# altair.net
KiCad netlist of a schematic drawn in EAGLE
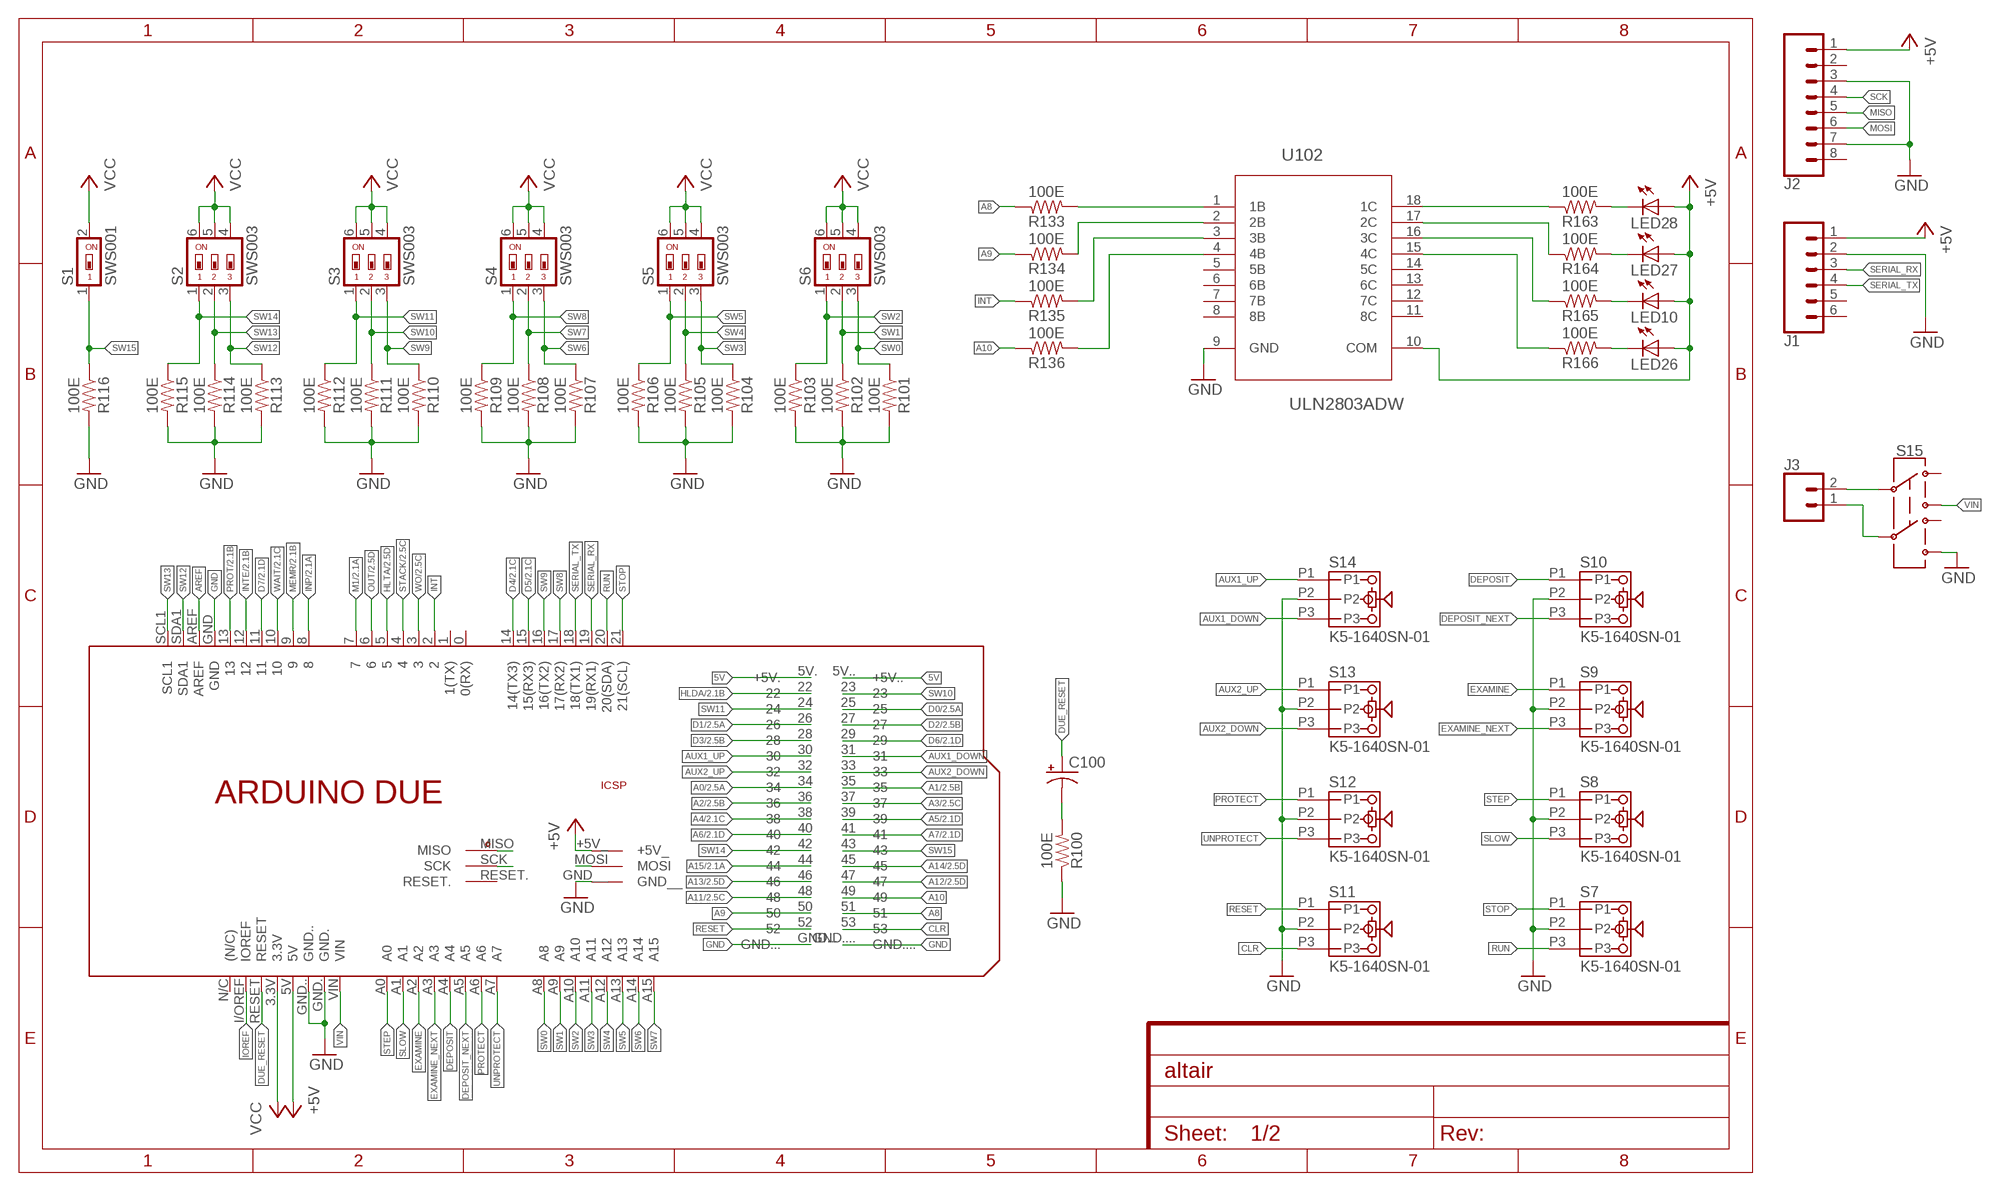
[diagram p0: schematic, sheet 1]
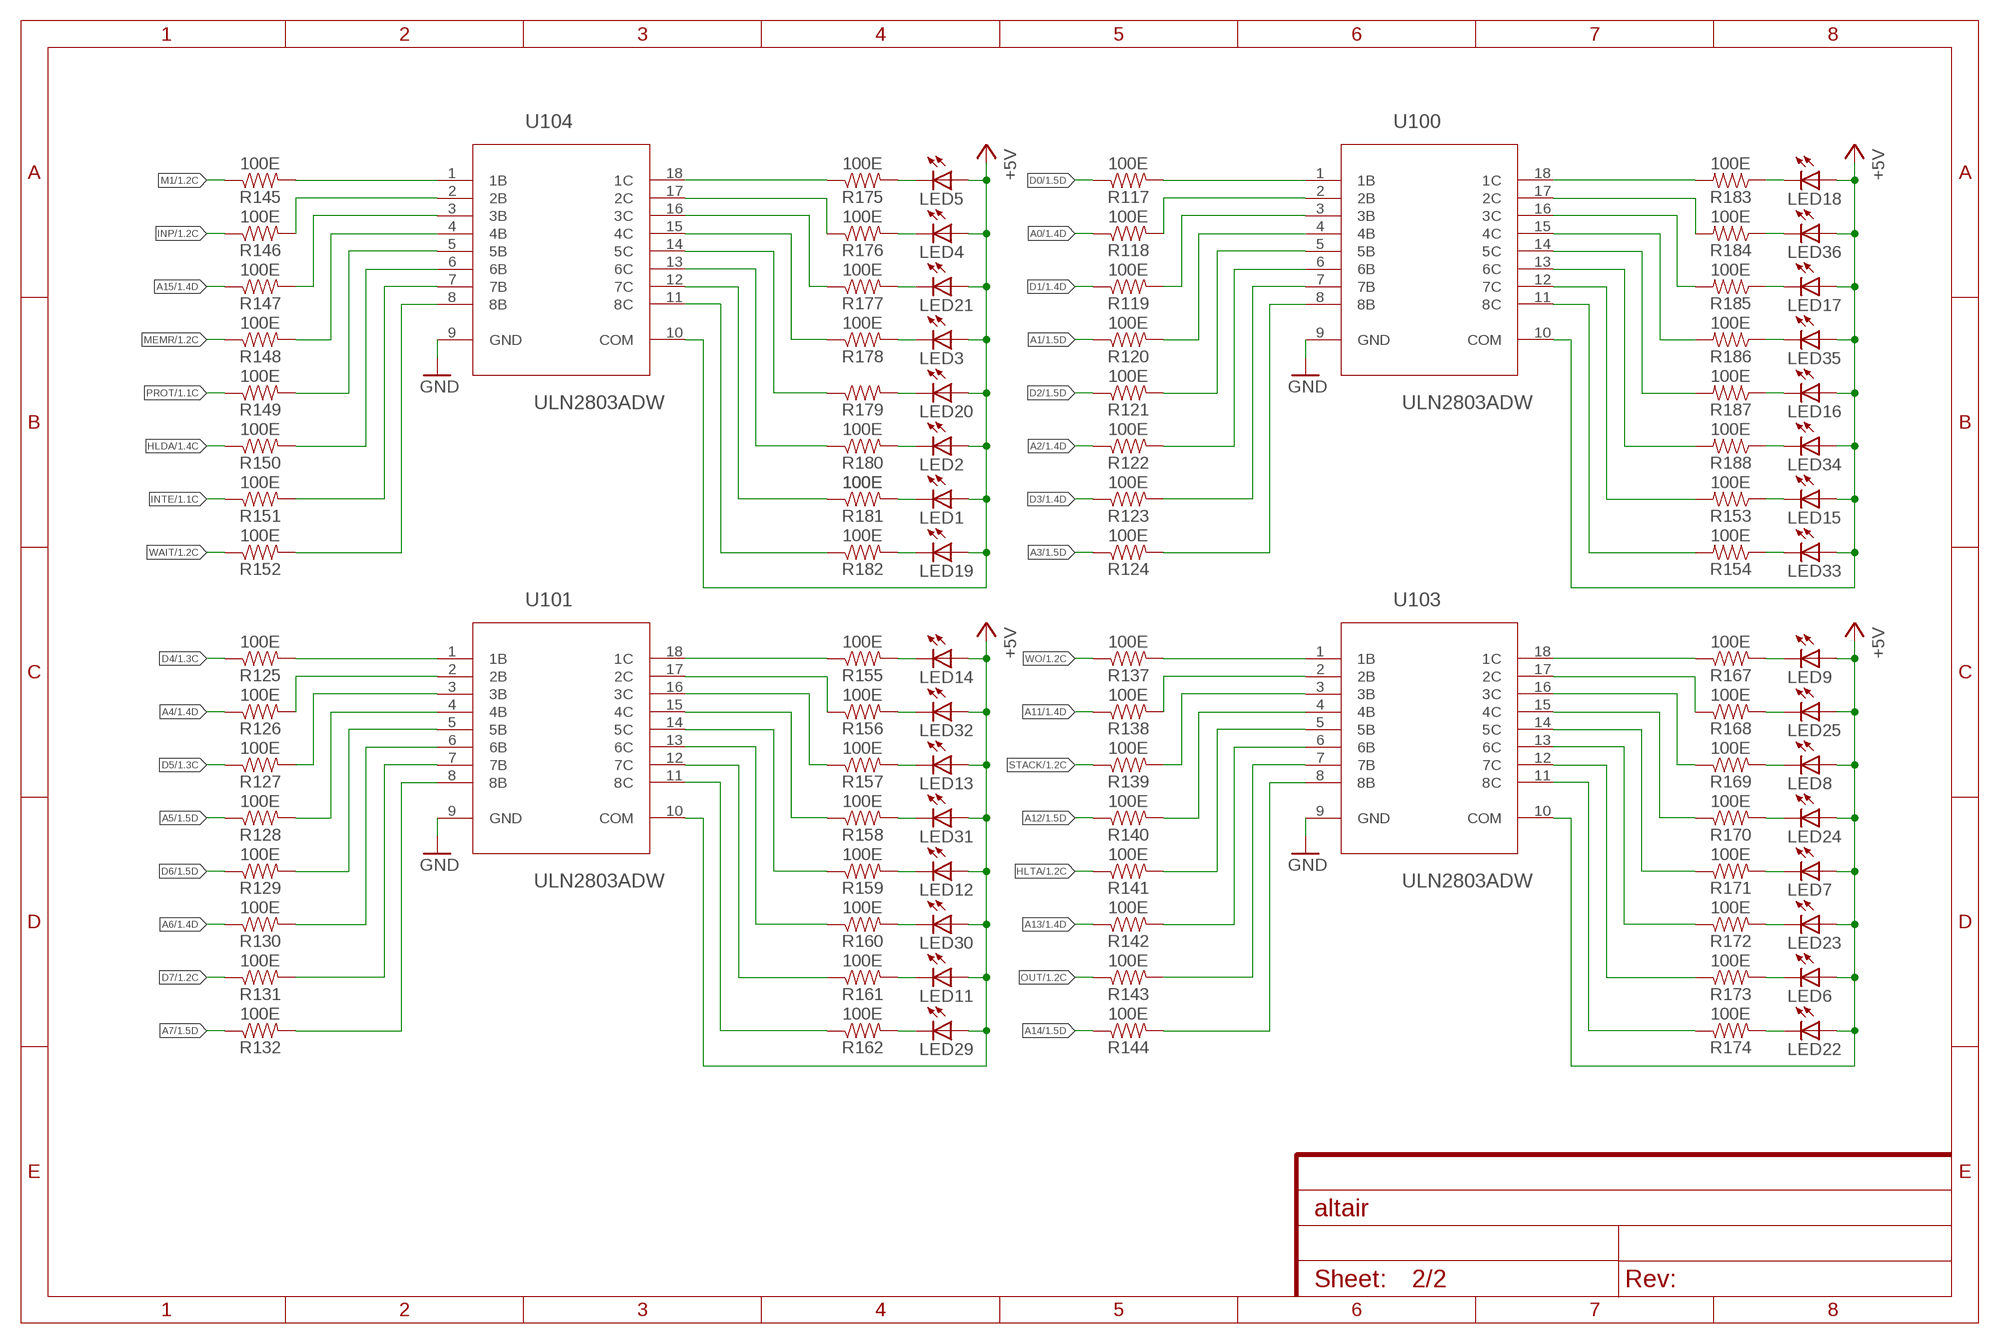
[diagram p1: schematic, sheet 2]

(export (version "E")
  (design (tool "Eeschema 10.0.6"))
  (components
    (comp (ref "C100")
      (value "CPOL-USD")
      (footprint "eagle-import:PANASONIC_D")
      (libsource (lib "eagle-import") (part "CPOL-USD"))
    )
    (comp (ref "J1")
      (value "CONN_06LOCK")
      (footprint "eagle-import:1X06_LOCK")
      (libsource (lib "eagle-import") (part "CONN_06LOCK"))
    )
    (comp (ref "J2")
      (value "CONN_08LOCK")
      (footprint "eagle-import:1X08_LOCK")
      (libsource (lib "eagle-import") (part "CONN_08LOCK"))
    )
    (comp (ref "J3")
      (value "CONN_02POLAR_LOCK")
      (footprint "eagle-import:MOLEX-1X2_LOCK")
      (libsource (lib "eagle-import") (part "CONN_02POLAR_LOCK"))
    )
    (comp (ref "LED10")
      (value "LEDCHIP-LED0805")
      (footprint "eagle-import:CHIP-LED0805")
      (libsource (lib "eagle-import") (part "LEDCHIP-LED0805"))
    )
    (comp (ref "LED26")
      (value "LEDCHIP-LED0805")
      (footprint "eagle-import:CHIP-LED0805")
      (libsource (lib "eagle-import") (part "LEDCHIP-LED0805"))
    )
    (comp (ref "LED27")
      (value "LEDCHIP-LED0805")
      (footprint "eagle-import:CHIP-LED0805")
      (libsource (lib "eagle-import") (part "LEDCHIP-LED0805"))
    )
    (comp (ref "LED28")
      (value "LEDCHIP-LED0805")
      (footprint "eagle-import:CHIP-LED0805")
      (libsource (lib "eagle-import") (part "LEDCHIP-LED0805"))
    )
    (comp (ref "PCB1")
      (value "ARDUINO_DUEARDUINO_DUE")
      (footprint "eagle-import:ARDUINO_MEGA2560")
      (libsource (lib "eagle-import") (part "ARDUINO_DUEARDUINO_DUE"))
    )
    (comp (ref "R100")
      (value "100E")
      (footprint "eagle-import:0805")
      (libsource (lib "eagle-import") (part "RESISTOR0805"))
    )
    (comp (ref "R101")
      (value "100E")
      (footprint "eagle-import:0805")
      (libsource (lib "eagle-import") (part "RESISTOR0805"))
    )
    (comp (ref "R102")
      (value "100E")
      (footprint "eagle-import:0805")
      (libsource (lib "eagle-import") (part "RESISTOR0805"))
    )
    (comp (ref "R103")
      (value "100E")
      (footprint "eagle-import:0805")
      (libsource (lib "eagle-import") (part "RESISTOR0805"))
    )
    (comp (ref "R104")
      (value "100E")
      (footprint "eagle-import:0805")
      (libsource (lib "eagle-import") (part "RESISTOR0805"))
    )
    (comp (ref "R105")
      (value "100E")
      (footprint "eagle-import:0805")
      (libsource (lib "eagle-import") (part "RESISTOR0805"))
    )
    (comp (ref "R106")
      (value "100E")
      (footprint "eagle-import:0805")
      (libsource (lib "eagle-import") (part "RESISTOR0805"))
    )
    (comp (ref "R107")
      (value "100E")
      (footprint "eagle-import:0805")
      (libsource (lib "eagle-import") (part "RESISTOR0805"))
    )
    (comp (ref "R108")
      (value "100E")
      (footprint "eagle-import:0805")
      (libsource (lib "eagle-import") (part "RESISTOR0805"))
    )
    (comp (ref "R109")
      (value "100E")
      (footprint "eagle-import:0805")
      (libsource (lib "eagle-import") (part "RESISTOR0805"))
    )
    (comp (ref "R110")
      (value "100E")
      (footprint "eagle-import:0805")
      (libsource (lib "eagle-import") (part "RESISTOR0805"))
    )
    (comp (ref "R111")
      (value "100E")
      (footprint "eagle-import:0805")
      (libsource (lib "eagle-import") (part "RESISTOR0805"))
    )
    (comp (ref "R112")
      (value "100E")
      (footprint "eagle-import:0805")
      (libsource (lib "eagle-import") (part "RESISTOR0805"))
    )
    (comp (ref "R113")
      (value "100E")
      (footprint "eagle-import:0805")
      (libsource (lib "eagle-import") (part "RESISTOR0805"))
    )
    (comp (ref "R114")
      (value "100E")
      (footprint "eagle-import:0805")
      (libsource (lib "eagle-import") (part "RESISTOR0805"))
    )
    (comp (ref "R115")
      (value "100E")
      (footprint "eagle-import:0805")
      (libsource (lib "eagle-import") (part "RESISTOR0805"))
    )
    (comp (ref "R116")
      (value "100E")
      (footprint "eagle-import:0805")
      (libsource (lib "eagle-import") (part "RESISTOR0805"))
    )
    (comp (ref "R133")
      (value "100E")
      (footprint "eagle-import:0805")
      (libsource (lib "eagle-import") (part "RESISTOR0805"))
    )
    (comp (ref "R134")
      (value "100E")
      (footprint "eagle-import:0805")
      (libsource (lib "eagle-import") (part "RESISTOR0805"))
    )
    (comp (ref "R135")
      (value "100E")
      (footprint "eagle-import:0805")
      (libsource (lib "eagle-import") (part "RESISTOR0805"))
    )
    (comp (ref "R136")
      (value "100E")
      (footprint "eagle-import:0805")
      (libsource (lib "eagle-import") (part "RESISTOR0805"))
    )
    (comp (ref "R163")
      (value "100E")
      (footprint "eagle-import:0805")
      (libsource (lib "eagle-import") (part "RESISTOR0805"))
    )
    (comp (ref "R164")
      (value "100E")
      (footprint "eagle-import:0805")
      (libsource (lib "eagle-import") (part "RESISTOR0805"))
    )
    (comp (ref "R165")
      (value "100E")
      (footprint "eagle-import:0805")
      (libsource (lib "eagle-import") (part "RESISTOR0805"))
    )
    (comp (ref "R166")
      (value "100E")
      (footprint "eagle-import:0805")
      (libsource (lib "eagle-import") (part "RESISTOR0805"))
    )
    (comp (ref "S1")
      (value "SWS001")
      (footprint "eagle-import:SMS-001")
      (libsource (lib "eagle-import") (part "SWS001"))
    )
    (comp (ref "S2")
      (value "SWS003")
      (footprint "eagle-import:SMS-003")
      (libsource (lib "eagle-import") (part "SWS003"))
    )
    (comp (ref "S3")
      (value "SWS003")
      (footprint "eagle-import:SMS-003")
      (libsource (lib "eagle-import") (part "SWS003"))
    )
    (comp (ref "S4")
      (value "SWS003")
      (footprint "eagle-import:SMS-003")
      (libsource (lib "eagle-import") (part "SWS003"))
    )
    (comp (ref "S5")
      (value "SWS003")
      (footprint "eagle-import:SMS-003")
      (libsource (lib "eagle-import") (part "SWS003"))
    )
    (comp (ref "S6")
      (value "SWS003")
      (footprint "eagle-import:SMS-003")
      (libsource (lib "eagle-import") (part "SWS003"))
    )
    (comp (ref "S7")
      (value "K5-1640SN-01")
      (footprint "eagle-import:K5-1640SN-01")
      (libsource (lib "eagle-import") (part "K5-1640SN-01"))
    )
    (comp (ref "S8")
      (value "K5-1640SN-01")
      (footprint "eagle-import:K5-1640SN-01")
      (libsource (lib "eagle-import") (part "K5-1640SN-01"))
    )
    (comp (ref "S9")
      (value "K5-1640SN-01")
      (footprint "eagle-import:K5-1640SN-01")
      (libsource (lib "eagle-import") (part "K5-1640SN-01"))
    )
    (comp (ref "S10")
      (value "K5-1640SN-01")
      (footprint "eagle-import:K5-1640SN-01")
      (libsource (lib "eagle-import") (part "K5-1640SN-01"))
    )
    (comp (ref "S11")
      (value "K5-1640SN-01")
      (footprint "eagle-import:K5-1640SN-01")
      (libsource (lib "eagle-import") (part "K5-1640SN-01"))
    )
    (comp (ref "S12")
      (value "K5-1640SN-01")
      (footprint "eagle-import:K5-1640SN-01")
      (libsource (lib "eagle-import") (part "K5-1640SN-01"))
    )
    (comp (ref "S13")
      (value "K5-1640SN-01")
      (footprint "eagle-import:K5-1640SN-01")
      (libsource (lib "eagle-import") (part "K5-1640SN-01"))
    )
    (comp (ref "S14")
      (value "K5-1640SN-01")
      (footprint "eagle-import:K5-1640SN-01")
      (libsource (lib "eagle-import") (part "K5-1640SN-01"))
    )
    (comp (ref "S15")
      (value "SWITCH-DPDT-SMD-AYZ0202")
      (footprint "eagle-import:SWITCH_DPDT_SMD_AYZ0202")
      (libsource (lib "eagle-import") (part "SWITCH-DPDT-SMD-AYZ0202"))
    )
    (comp (ref "U102")
      (value "ULN2803ADW")
      (footprint "eagle-import:SOIC127P1030X265-18N")
      (libsource (lib "eagle-import") (part "ULN2803ADW"))
    )
    (comp (ref "LED1")
      (value "LEDCHIP-LED0805")
      (footprint "eagle-import:CHIP-LED0805")
      (libsource (lib "eagle-import") (part "LEDCHIP-LED0805"))
    )
    (comp (ref "LED2")
      (value "LEDCHIP-LED0805")
      (footprint "eagle-import:CHIP-LED0805")
      (libsource (lib "eagle-import") (part "LEDCHIP-LED0805"))
    )
    (comp (ref "LED3")
      (value "LEDCHIP-LED0805")
      (footprint "eagle-import:CHIP-LED0805")
      (libsource (lib "eagle-import") (part "LEDCHIP-LED0805"))
    )
    (comp (ref "LED4")
      (value "LEDCHIP-LED0805")
      (footprint "eagle-import:CHIP-LED0805")
      (libsource (lib "eagle-import") (part "LEDCHIP-LED0805"))
    )
    (comp (ref "LED5")
      (value "LEDCHIP-LED0805")
      (footprint "eagle-import:CHIP-LED0805")
      (libsource (lib "eagle-import") (part "LEDCHIP-LED0805"))
    )
    (comp (ref "LED6")
      (value "LEDCHIP-LED0805")
      (footprint "eagle-import:CHIP-LED0805")
      (libsource (lib "eagle-import") (part "LEDCHIP-LED0805"))
    )
    (comp (ref "LED7")
      (value "LEDCHIP-LED0805")
      (footprint "eagle-import:CHIP-LED0805")
      (libsource (lib "eagle-import") (part "LEDCHIP-LED0805"))
    )
    (comp (ref "LED8")
      (value "LEDCHIP-LED0805")
      (footprint "eagle-import:CHIP-LED0805")
      (libsource (lib "eagle-import") (part "LEDCHIP-LED0805"))
    )
    (comp (ref "LED9")
      (value "LEDCHIP-LED0805")
      (footprint "eagle-import:CHIP-LED0805")
      (libsource (lib "eagle-import") (part "LEDCHIP-LED0805"))
    )
    (comp (ref "LED11")
      (value "LEDCHIP-LED0805")
      (footprint "eagle-import:CHIP-LED0805")
      (libsource (lib "eagle-import") (part "LEDCHIP-LED0805"))
    )
    (comp (ref "LED12")
      (value "LEDCHIP-LED0805")
      (footprint "eagle-import:CHIP-LED0805")
      (libsource (lib "eagle-import") (part "LEDCHIP-LED0805"))
    )
    (comp (ref "LED13")
      (value "LEDCHIP-LED0805")
      (footprint "eagle-import:CHIP-LED0805")
      (libsource (lib "eagle-import") (part "LEDCHIP-LED0805"))
    )
    (comp (ref "LED14")
      (value "LEDCHIP-LED0805")
      (footprint "eagle-import:CHIP-LED0805")
      (libsource (lib "eagle-import") (part "LEDCHIP-LED0805"))
    )
    (comp (ref "LED15")
      (value "LEDCHIP-LED0805")
      (footprint "eagle-import:CHIP-LED0805")
      (libsource (lib "eagle-import") (part "LEDCHIP-LED0805"))
    )
    (comp (ref "LED16")
      (value "LEDCHIP-LED0805")
      (footprint "eagle-import:CHIP-LED0805")
      (libsource (lib "eagle-import") (part "LEDCHIP-LED0805"))
    )
    (comp (ref "LED17")
      (value "LEDCHIP-LED0805")
      (footprint "eagle-import:CHIP-LED0805")
      (libsource (lib "eagle-import") (part "LEDCHIP-LED0805"))
    )
    (comp (ref "LED18")
      (value "LEDCHIP-LED0805")
      (footprint "eagle-import:CHIP-LED0805")
      (libsource (lib "eagle-import") (part "LEDCHIP-LED0805"))
    )
    (comp (ref "LED19")
      (value "LEDCHIP-LED0805")
      (footprint "eagle-import:CHIP-LED0805")
      (libsource (lib "eagle-import") (part "LEDCHIP-LED0805"))
    )
    (comp (ref "LED20")
      (value "LEDCHIP-LED0805")
      (footprint "eagle-import:CHIP-LED0805")
      (libsource (lib "eagle-import") (part "LEDCHIP-LED0805"))
    )
    (comp (ref "LED21")
      (value "LEDCHIP-LED0805")
      (footprint "eagle-import:CHIP-LED0805")
      (libsource (lib "eagle-import") (part "LEDCHIP-LED0805"))
    )
    (comp (ref "LED22")
      (value "LEDCHIP-LED0805")
      (footprint "eagle-import:CHIP-LED0805")
      (libsource (lib "eagle-import") (part "LEDCHIP-LED0805"))
    )
    (comp (ref "LED23")
      (value "LEDCHIP-LED0805")
      (footprint "eagle-import:CHIP-LED0805")
      (libsource (lib "eagle-import") (part "LEDCHIP-LED0805"))
    )
    (comp (ref "LED24")
      (value "LEDCHIP-LED0805")
      (footprint "eagle-import:CHIP-LED0805")
      (libsource (lib "eagle-import") (part "LEDCHIP-LED0805"))
    )
    (comp (ref "LED25")
      (value "LEDCHIP-LED0805")
      (footprint "eagle-import:CHIP-LED0805")
      (libsource (lib "eagle-import") (part "LEDCHIP-LED0805"))
    )
    (comp (ref "LED29")
      (value "LEDCHIP-LED0805")
      (footprint "eagle-import:CHIP-LED0805")
      (libsource (lib "eagle-import") (part "LEDCHIP-LED0805"))
    )
    (comp (ref "LED30")
      (value "LEDCHIP-LED0805")
      (footprint "eagle-import:CHIP-LED0805")
      (libsource (lib "eagle-import") (part "LEDCHIP-LED0805"))
    )
    (comp (ref "LED31")
      (value "LEDCHIP-LED0805")
      (footprint "eagle-import:CHIP-LED0805")
      (libsource (lib "eagle-import") (part "LEDCHIP-LED0805"))
    )
    (comp (ref "LED32")
      (value "LEDCHIP-LED0805")
      (footprint "eagle-import:CHIP-LED0805")
      (libsource (lib "eagle-import") (part "LEDCHIP-LED0805"))
    )
    (comp (ref "LED33")
      (value "LEDCHIP-LED0805")
      (footprint "eagle-import:CHIP-LED0805")
      (libsource (lib "eagle-import") (part "LEDCHIP-LED0805"))
    )
    (comp (ref "LED34")
      (value "LEDCHIP-LED0805")
      (footprint "eagle-import:CHIP-LED0805")
      (libsource (lib "eagle-import") (part "LEDCHIP-LED0805"))
    )
    (comp (ref "LED35")
      (value "LEDCHIP-LED0805")
      (footprint "eagle-import:CHIP-LED0805")
      (libsource (lib "eagle-import") (part "LEDCHIP-LED0805"))
    )
    (comp (ref "LED36")
      (value "LEDCHIP-LED0805")
      (footprint "eagle-import:CHIP-LED0805")
      (libsource (lib "eagle-import") (part "LEDCHIP-LED0805"))
    )
    (comp (ref "R117")
      (value "100E")
      (footprint "eagle-import:0805")
      (libsource (lib "eagle-import") (part "RESISTOR0805"))
    )
    (comp (ref "R118")
      (value "100E")
      (footprint "eagle-import:0805")
      (libsource (lib "eagle-import") (part "RESISTOR0805"))
    )
    (comp (ref "R119")
      (value "100E")
      (footprint "eagle-import:0805")
      (libsource (lib "eagle-import") (part "RESISTOR0805"))
    )
    (comp (ref "R120")
      (value "100E")
      (footprint "eagle-import:0805")
      (libsource (lib "eagle-import") (part "RESISTOR0805"))
    )
    (comp (ref "R121")
      (value "100E")
      (footprint "eagle-import:0805")
      (libsource (lib "eagle-import") (part "RESISTOR0805"))
    )
    (comp (ref "R122")
      (value "100E")
      (footprint "eagle-import:0805")
      (libsource (lib "eagle-import") (part "RESISTOR0805"))
    )
    (comp (ref "R123")
      (value "100E")
      (footprint "eagle-import:0805")
      (libsource (lib "eagle-import") (part "RESISTOR0805"))
    )
    (comp (ref "R124")
      (value "100E")
      (footprint "eagle-import:0805")
      (libsource (lib "eagle-import") (part "RESISTOR0805"))
    )
    (comp (ref "R125")
      (value "100E")
      (footprint "eagle-import:0805")
      (libsource (lib "eagle-import") (part "RESISTOR0805"))
    )
    (comp (ref "R126")
      (value "100E")
      (footprint "eagle-import:0805")
      (libsource (lib "eagle-import") (part "RESISTOR0805"))
    )
    (comp (ref "R127")
      (value "100E")
      (footprint "eagle-import:0805")
      (libsource (lib "eagle-import") (part "RESISTOR0805"))
    )
    (comp (ref "R128")
      (value "100E")
      (footprint "eagle-import:0805")
      (libsource (lib "eagle-import") (part "RESISTOR0805"))
    )
    (comp (ref "R129")
      (value "100E")
      (footprint "eagle-import:0805")
      (libsource (lib "eagle-import") (part "RESISTOR0805"))
    )
    (comp (ref "R130")
      (value "100E")
      (footprint "eagle-import:0805")
      (libsource (lib "eagle-import") (part "RESISTOR0805"))
    )
    (comp (ref "R131")
      (value "100E")
      (footprint "eagle-import:0805")
      (libsource (lib "eagle-import") (part "RESISTOR0805"))
    )
    (comp (ref "R132")
      (value "100E")
      (footprint "eagle-import:0805")
      (libsource (lib "eagle-import") (part "RESISTOR0805"))
    )
    (comp (ref "R137")
      (value "100E")
      (footprint "eagle-import:0805")
      (libsource (lib "eagle-import") (part "RESISTOR0805"))
    )
    (comp (ref "R138")
      (value "100E")
      (footprint "eagle-import:0805")
      (libsource (lib "eagle-import") (part "RESISTOR0805"))
    )
    (comp (ref "R139")
      (value "100E")
      (footprint "eagle-import:0805")
      (libsource (lib "eagle-import") (part "RESISTOR0805"))
    )
    (comp (ref "R140")
      (value "100E")
      (footprint "eagle-import:0805")
      (libsource (lib "eagle-import") (part "RESISTOR0805"))
    )
    (comp (ref "R141")
      (value "100E")
      (footprint "eagle-import:0805")
      (libsource (lib "eagle-import") (part "RESISTOR0805"))
    )
    (comp (ref "R142")
      (value "100E")
      (footprint "eagle-import:0805")
      (libsource (lib "eagle-import") (part "RESISTOR0805"))
    )
    (comp (ref "R143")
      (value "100E")
      (footprint "eagle-import:0805")
      (libsource (lib "eagle-import") (part "RESISTOR0805"))
    )
    (comp (ref "R144")
      (value "100E")
      (footprint "eagle-import:0805")
      (libsource (lib "eagle-import") (part "RESISTOR0805"))
    )
    (comp (ref "R145")
      (value "100E")
      (footprint "eagle-import:0805")
      (libsource (lib "eagle-import") (part "RESISTOR0805"))
    )
    (comp (ref "R146")
      (value "100E")
      (footprint "eagle-import:0805")
      (libsource (lib "eagle-import") (part "RESISTOR0805"))
    )
    (comp (ref "R147")
      (value "100E")
      (footprint "eagle-import:0805")
      (libsource (lib "eagle-import") (part "RESISTOR0805"))
    )
    (comp (ref "R148")
      (value "100E")
      (footprint "eagle-import:0805")
      (libsource (lib "eagle-import") (part "RESISTOR0805"))
    )
    (comp (ref "R149")
      (value "100E")
      (footprint "eagle-import:0805")
      (libsource (lib "eagle-import") (part "RESISTOR0805"))
    )
    (comp (ref "R150")
      (value "100E")
      (footprint "eagle-import:0805")
      (libsource (lib "eagle-import") (part "RESISTOR0805"))
    )
    (comp (ref "R151")
      (value "100E")
      (footprint "eagle-import:0805")
      (libsource (lib "eagle-import") (part "RESISTOR0805"))
    )
    (comp (ref "R152")
      (value "100E")
      (footprint "eagle-import:0805")
      (libsource (lib "eagle-import") (part "RESISTOR0805"))
    )
    (comp (ref "R153")
      (value "100E")
      (footprint "eagle-import:0805")
      (libsource (lib "eagle-import") (part "RESISTOR0805"))
    )
    (comp (ref "R154")
      (value "100E")
      (footprint "eagle-import:0805")
      (libsource (lib "eagle-import") (part "RESISTOR0805"))
    )
    (comp (ref "R155")
      (value "100E")
      (footprint "eagle-import:0805")
      (libsource (lib "eagle-import") (part "RESISTOR0805"))
    )
    (comp (ref "R156")
      (value "100E")
      (footprint "eagle-import:0805")
      (libsource (lib "eagle-import") (part "RESISTOR0805"))
    )
    (comp (ref "R157")
      (value "100E")
      (footprint "eagle-import:0805")
      (libsource (lib "eagle-import") (part "RESISTOR0805"))
    )
    (comp (ref "R158")
      (value "100E")
      (footprint "eagle-import:0805")
      (libsource (lib "eagle-import") (part "RESISTOR0805"))
    )
    (comp (ref "R159")
      (value "100E")
      (footprint "eagle-import:0805")
      (libsource (lib "eagle-import") (part "RESISTOR0805"))
    )
    (comp (ref "R160")
      (value "100E")
      (footprint "eagle-import:0805")
      (libsource (lib "eagle-import") (part "RESISTOR0805"))
    )
    (comp (ref "R161")
      (value "100E")
      (footprint "eagle-import:0805")
      (libsource (lib "eagle-import") (part "RESISTOR0805"))
    )
    (comp (ref "R162")
      (value "100E")
      (footprint "eagle-import:0805")
      (libsource (lib "eagle-import") (part "RESISTOR0805"))
    )
    (comp (ref "R167")
      (value "100E")
      (footprint "eagle-import:0805")
      (libsource (lib "eagle-import") (part "RESISTOR0805"))
    )
    (comp (ref "R168")
      (value "100E")
      (footprint "eagle-import:0805")
      (libsource (lib "eagle-import") (part "RESISTOR0805"))
    )
    (comp (ref "R169")
      (value "100E")
      (footprint "eagle-import:0805")
      (libsource (lib "eagle-import") (part "RESISTOR0805"))
    )
    (comp (ref "R170")
      (value "100E")
      (footprint "eagle-import:0805")
      (libsource (lib "eagle-import") (part "RESISTOR0805"))
    )
    (comp (ref "R171")
      (value "100E")
      (footprint "eagle-import:0805")
      (libsource (lib "eagle-import") (part "RESISTOR0805"))
    )
    (comp (ref "R172")
      (value "100E")
      (footprint "eagle-import:0805")
      (libsource (lib "eagle-import") (part "RESISTOR0805"))
    )
    (comp (ref "R173")
      (value "100E")
      (footprint "eagle-import:0805")
      (libsource (lib "eagle-import") (part "RESISTOR0805"))
    )
    (comp (ref "R174")
      (value "100E")
      (footprint "eagle-import:0805")
      (libsource (lib "eagle-import") (part "RESISTOR0805"))
    )
    (comp (ref "R175")
      (value "100E")
      (footprint "eagle-import:0805")
      (libsource (lib "eagle-import") (part "RESISTOR0805"))
    )
    (comp (ref "R176")
      (value "100E")
      (footprint "eagle-import:0805")
      (libsource (lib "eagle-import") (part "RESISTOR0805"))
    )
    (comp (ref "R177")
      (value "100E")
      (footprint "eagle-import:0805")
      (libsource (lib "eagle-import") (part "RESISTOR0805"))
    )
    (comp (ref "R178")
      (value "100E")
      (footprint "eagle-import:0805")
      (libsource (lib "eagle-import") (part "RESISTOR0805"))
    )
    (comp (ref "R179")
      (value "100E")
      (footprint "eagle-import:0805")
      (libsource (lib "eagle-import") (part "RESISTOR0805"))
    )
    (comp (ref "R180")
      (value "100E")
      (footprint "eagle-import:0805")
      (libsource (lib "eagle-import") (part "RESISTOR0805"))
    )
    (comp (ref "R181")
      (value "100E")
      (footprint "eagle-import:0805")
      (libsource (lib "eagle-import") (part "RESISTOR0805"))
    )
    (comp (ref "R182")
      (value "100E")
      (footprint "eagle-import:0805")
      (libsource (lib "eagle-import") (part "RESISTOR0805"))
    )
    (comp (ref "R183")
      (value "100E")
      (footprint "eagle-import:0805")
      (libsource (lib "eagle-import") (part "RESISTOR0805"))
    )
    (comp (ref "R184")
      (value "100E")
      (footprint "eagle-import:0805")
      (libsource (lib "eagle-import") (part "RESISTOR0805"))
    )
    (comp (ref "R185")
      (value "100E")
      (footprint "eagle-import:0805")
      (libsource (lib "eagle-import") (part "RESISTOR0805"))
    )
    (comp (ref "R186")
      (value "100E")
      (footprint "eagle-import:0805")
      (libsource (lib "eagle-import") (part "RESISTOR0805"))
    )
    (comp (ref "R187")
      (value "100E")
      (footprint "eagle-import:0805")
      (libsource (lib "eagle-import") (part "RESISTOR0805"))
    )
    (comp (ref "R188")
      (value "100E")
      (footprint "eagle-import:0805")
      (libsource (lib "eagle-import") (part "RESISTOR0805"))
    )
    (comp (ref "U100")
      (value "ULN2803ADW")
      (footprint "eagle-import:SOIC127P1030X265-18N")
      (libsource (lib "eagle-import") (part "ULN2803ADW"))
    )
    (comp (ref "U101")
      (value "ULN2803ADW")
      (footprint "eagle-import:SOIC127P1030X265-18N")
      (libsource (lib "eagle-import") (part "ULN2803ADW"))
    )
    (comp (ref "U103")
      (value "ULN2803ADW")
      (footprint "eagle-import:SOIC127P1030X265-18N")
      (libsource (lib "eagle-import") (part "ULN2803ADW"))
    )
    (comp (ref "U104")
      (value "ULN2803ADW")
      (footprint "eagle-import:SOIC127P1030X265-18N")
      (libsource (lib "eagle-import") (part "ULN2803ADW"))
    )
  )
  (nets
    (net (code "1") (name "+5V") (class "Default")
      (node (ref "J1") (pin "1") (pinfunction "1_1") (pintype "passive"))
      (node (ref "J2") (pin "1") (pinfunction "1_1") (pintype "passive"))
      (node (ref "LED1") (pin "A") (pinfunction "A_A") (pintype "passive"))
      (node (ref "LED10") (pin "A") (pinfunction "A_A") (pintype "passive"))
      (node (ref "LED11") (pin "A") (pinfunction "A_A") (pintype "passive"))
      (node (ref "LED12") (pin "A") (pinfunction "A_A") (pintype "passive"))
      (node (ref "LED13") (pin "A") (pinfunction "A_A") (pintype "passive"))
      (node (ref "LED14") (pin "A") (pinfunction "A_A") (pintype "passive"))
      (node (ref "LED15") (pin "A") (pinfunction "A_A") (pintype "passive"))
      (node (ref "LED16") (pin "A") (pinfunction "A_A") (pintype "passive"))
      (node (ref "LED17") (pin "A") (pinfunction "A_A") (pintype "passive"))
      (node (ref "LED18") (pin "A") (pinfunction "A_A") (pintype "passive"))
      (node (ref "LED19") (pin "A") (pinfunction "A_A") (pintype "passive"))
      (node (ref "LED2") (pin "A") (pinfunction "A_A") (pintype "passive"))
      (node (ref "LED20") (pin "A") (pinfunction "A_A") (pintype "passive"))
      (node (ref "LED21") (pin "A") (pinfunction "A_A") (pintype "passive"))
      (node (ref "LED22") (pin "A") (pinfunction "A_A") (pintype "passive"))
      (node (ref "LED23") (pin "A") (pinfunction "A_A") (pintype "passive"))
      (node (ref "LED24") (pin "A") (pinfunction "A_A") (pintype "passive"))
      (node (ref "LED25") (pin "A") (pinfunction "A_A") (pintype "passive"))
      (node (ref "LED26") (pin "A") (pinfunction "A_A") (pintype "passive"))
      (node (ref "LED27") (pin "A") (pinfunction "A_A") (pintype "passive"))
      (node (ref "LED28") (pin "A") (pinfunction "A_A") (pintype "passive"))
      (node (ref "LED29") (pin "A") (pinfunction "A_A") (pintype "passive"))
      (node (ref "LED3") (pin "A") (pinfunction "A_A") (pintype "passive"))
      (node (ref "LED30") (pin "A") (pinfunction "A_A") (pintype "passive"))
      (node (ref "LED31") (pin "A") (pinfunction "A_A") (pintype "passive"))
      (node (ref "LED32") (pin "A") (pinfunction "A_A") (pintype "passive"))
      (node (ref "LED33") (pin "A") (pinfunction "A_A") (pintype "passive"))
      (node (ref "LED34") (pin "A") (pinfunction "A_A") (pintype "passive"))
      (node (ref "LED35") (pin "A") (pinfunction "A_A") (pintype "passive"))
      (node (ref "LED36") (pin "A") (pinfunction "A_A") (pintype "passive"))
      (node (ref "LED4") (pin "A") (pinfunction "A_A") (pintype "passive"))
      (node (ref "LED5") (pin "A") (pinfunction "A_A") (pintype "passive"))
      (node (ref "LED6") (pin "A") (pinfunction "A_A") (pintype "passive"))
      (node (ref "LED7") (pin "A") (pinfunction "A_A") (pintype "passive"))
      (node (ref "LED8") (pin "A") (pinfunction "A_A") (pintype "passive"))
      (node (ref "LED9") (pin "A") (pinfunction "A_A") (pintype "passive"))
      (node (ref "PCB1") (pin "+5V_") (pinfunction "+5V__+5V_") (pintype "bidirectional"))
      (node (ref "PCB1") (pin "5V") (pinfunction "5V_5V") (pintype "bidirectional"))
      (node (ref "U100") (pin "10") (pinfunction "COM_10") (pintype "output"))
      (node (ref "U101") (pin "10") (pinfunction "COM_10") (pintype "output"))
      (node (ref "U102") (pin "10") (pinfunction "COM_10") (pintype "output"))
      (node (ref "U103") (pin "10") (pinfunction "COM_10") (pintype "output"))
      (node (ref "U104") (pin "10") (pinfunction "COM_10") (pintype "output"))
    )
    (net (code "2") (name "5V") (class "Default")
      (node (ref "PCB1") (pin "5V.") (pinfunction "+5V._5V.") (pintype "bidirectional"))
      (node (ref "PCB1") (pin "5V..") (pinfunction "+5V.._5V..") (pintype "bidirectional"))
    )
    (net (code "3") (name "A0") (class "Default")
      (node (ref "PCB1") (pin "34") (pinfunction "34_34") (pintype "bidirectional"))
      (node (ref "R118") (pin "1") (pinfunction "1_1") (pintype "passive"))
    )
    (net (code "4") (name "A1") (class "Default")
      (node (ref "PCB1") (pin "35") (pinfunction "35_35") (pintype "bidirectional"))
      (node (ref "R120") (pin "1") (pinfunction "1_1") (pintype "passive"))
    )
    (net (code "5") (name "A2") (class "Default")
      (node (ref "PCB1") (pin "36") (pinfunction "36_36") (pintype "bidirectional"))
      (node (ref "R122") (pin "1") (pinfunction "1_1") (pintype "passive"))
    )
    (net (code "6") (name "A3") (class "Default")
      (node (ref "PCB1") (pin "37") (pinfunction "37_37") (pintype "bidirectional"))
      (node (ref "R124") (pin "1") (pinfunction "1_1") (pintype "passive"))
    )
    (net (code "7") (name "A4") (class "Default")
      (node (ref "PCB1") (pin "38") (pinfunction "38_38") (pintype "bidirectional"))
      (node (ref "R126") (pin "1") (pinfunction "1_1") (pintype "passive"))
    )
    (net (code "8") (name "A5") (class "Default")
      (node (ref "PCB1") (pin "39") (pinfunction "39_39") (pintype "bidirectional"))
      (node (ref "R128") (pin "1") (pinfunction "1_1") (pintype "passive"))
    )
    (net (code "9") (name "A6") (class "Default")
      (node (ref "PCB1") (pin "40") (pinfunction "40_40") (pintype "bidirectional"))
      (node (ref "R130") (pin "1") (pinfunction "1_1") (pintype "passive"))
    )
    (net (code "10") (name "A7") (class "Default")
      (node (ref "PCB1") (pin "41") (pinfunction "41_41") (pintype "bidirectional"))
      (node (ref "R132") (pin "1") (pinfunction "1_1") (pintype "passive"))
    )
    (net (code "11") (name "A8") (class "Default")
      (node (ref "PCB1") (pin "51") (pinfunction "51_51") (pintype "bidirectional"))
      (node (ref "R133") (pin "1") (pinfunction "1_1") (pintype "passive"))
    )
    (net (code "12") (name "A9") (class "Default")
      (node (ref "PCB1") (pin "50") (pinfunction "50_50") (pintype "bidirectional"))
      (node (ref "R134") (pin "1") (pinfunction "1_1") (pintype "passive"))
    )
    (net (code "13") (name "A10") (class "Default")
      (node (ref "PCB1") (pin "49") (pinfunction "49_49") (pintype "bidirectional"))
      (node (ref "R136") (pin "1") (pinfunction "1_1") (pintype "passive"))
    )
    (net (code "14") (name "A11") (class "Default")
      (node (ref "PCB1") (pin "48") (pinfunction "48_48") (pintype "bidirectional"))
      (node (ref "R138") (pin "1") (pinfunction "1_1") (pintype "passive"))
    )
    (net (code "15") (name "A12") (class "Default")
      (node (ref "PCB1") (pin "47") (pinfunction "47_47") (pintype "bidirectional"))
      (node (ref "R140") (pin "1") (pinfunction "1_1") (pintype "passive"))
    )
    (net (code "16") (name "A13") (class "Default")
      (node (ref "PCB1") (pin "46") (pinfunction "46_46") (pintype "bidirectional"))
      (node (ref "R142") (pin "1") (pinfunction "1_1") (pintype "passive"))
    )
    (net (code "17") (name "A14") (class "Default")
      (node (ref "PCB1") (pin "45") (pinfunction "45_45") (pintype "bidirectional"))
      (node (ref "R144") (pin "1") (pinfunction "1_1") (pintype "passive"))
    )
    (net (code "18") (name "A15") (class "Default")
      (node (ref "PCB1") (pin "44") (pinfunction "44_44") (pintype "bidirectional"))
      (node (ref "R147") (pin "1") (pinfunction "1_1") (pintype "passive"))
    )
    (net (code "19") (name "AREF") (class "Default")
      (node (ref "PCB1") (pin "AREF") (pinfunction "AREF_AREF") (pintype "bidirectional"))
    )
    (net (code "20") (name "AUX1_DOWN") (class "Default")
      (node (ref "PCB1") (pin "31") (pinfunction "31_31") (pintype "bidirectional"))
      (node (ref "S14") (pin "P3") (pinfunction "P3_P3") (pintype "bidirectional"))
    )
    (net (code "21") (name "AUX1_UP") (class "Default")
      (node (ref "PCB1") (pin "30") (pinfunction "30_30") (pintype "bidirectional"))
      (node (ref "S14") (pin "P1") (pinfunction "P1_P1") (pintype "bidirectional"))
    )
    (net (code "22") (name "AUX2_DOWN") (class "Default")
      (node (ref "PCB1") (pin "33") (pinfunction "33_33") (pintype "bidirectional"))
      (node (ref "S13") (pin "P3") (pinfunction "P3_P3") (pintype "bidirectional"))
    )
    (net (code "23") (name "AUX2_UP") (class "Default")
      (node (ref "PCB1") (pin "32") (pinfunction "32_32") (pintype "bidirectional"))
      (node (ref "S13") (pin "P1") (pinfunction "P1_P1") (pintype "bidirectional"))
    )
    (net (code "24") (name "CLR") (class "Default")
      (node (ref "PCB1") (pin "53") (pinfunction "53_53") (pintype "bidirectional"))
      (node (ref "S11") (pin "P3") (pinfunction "P3_P3") (pintype "bidirectional"))
    )
    (net (code "25") (name "D0") (class "Default")
      (node (ref "PCB1") (pin "25") (pinfunction "25_25") (pintype "bidirectional"))
      (node (ref "R117") (pin "1") (pinfunction "1_1") (pintype "passive"))
    )
    (net (code "26") (name "D1") (class "Default")
      (node (ref "PCB1") (pin "26") (pinfunction "26_26") (pintype "bidirectional"))
      (node (ref "R119") (pin "1") (pinfunction "1_1") (pintype "passive"))
    )
    (net (code "27") (name "D2") (class "Default")
      (node (ref "PCB1") (pin "27") (pinfunction "27_27") (pintype "bidirectional"))
      (node (ref "R121") (pin "1") (pinfunction "1_1") (pintype "passive"))
    )
    (net (code "28") (name "D3") (class "Default")
      (node (ref "PCB1") (pin "28") (pinfunction "28_28") (pintype "bidirectional"))
      (node (ref "R123") (pin "1") (pinfunction "1_1") (pintype "passive"))
    )
    (net (code "29") (name "D4") (class "Default")
      (node (ref "PCB1") (pin "14") (pinfunction "14(TX3)_14") (pintype "bidirectional"))
      (node (ref "R125") (pin "1") (pinfunction "1_1") (pintype "passive"))
    )
    (net (code "30") (name "D5") (class "Default")
      (node (ref "PCB1") (pin "15") (pinfunction "15(RX3)_15") (pintype "bidirectional"))
      (node (ref "R127") (pin "1") (pinfunction "1_1") (pintype "passive"))
    )
    (net (code "31") (name "D6") (class "Default")
      (node (ref "PCB1") (pin "29") (pinfunction "29_29") (pintype "bidirectional"))
      (node (ref "R129") (pin "1") (pinfunction "1_1") (pintype "passive"))
    )
    (net (code "32") (name "D7") (class "Default")
      (node (ref "PCB1") (pin "11") (pinfunction "11_11") (pintype "bidirectional"))
      (node (ref "R131") (pin "1") (pinfunction "1_1") (pintype "passive"))
    )
    (net (code "33") (name "DEPOSIT") (class "Default")
      (node (ref "PCB1") (pin "A4") (pinfunction "A4_A4") (pintype "bidirectional"))
      (node (ref "S10") (pin "P1") (pinfunction "P1_P1") (pintype "bidirectional"))
    )
    (net (code "34") (name "DEPOSIT_NEXT") (class "Default")
      (node (ref "PCB1") (pin "A5") (pinfunction "A5_A5") (pintype "bidirectional"))
      (node (ref "S10") (pin "P3") (pinfunction "P3_P3") (pintype "bidirectional"))
    )
    (net (code "35") (name "DUE_RESET") (class "Default")
      (node (ref "C100") (pin "+") (pinfunction "+_+") (pintype "passive"))
      (node (ref "PCB1") (pin "RESET") (pinfunction "RESET_RESET") (pintype "bidirectional"))
    )
    (net (code "36") (name "EXAMINE") (class "Default")
      (node (ref "PCB1") (pin "A2") (pinfunction "A2_A2") (pintype "bidirectional"))
      (node (ref "S9") (pin "P1") (pinfunction "P1_P1") (pintype "bidirectional"))
    )
    (net (code "37") (name "EXAMINE_NEXT") (class "Default")
      (node (ref "PCB1") (pin "A3") (pinfunction "A3_A3") (pintype "bidirectional"))
      (node (ref "S9") (pin "P3") (pinfunction "P3_P3") (pintype "bidirectional"))
    )
    (net (code "38") (name "GND") (class "Default")
      (node (ref "J1") (pin "2") (pinfunction "2_2") (pintype "passive"))
      (node (ref "J2") (pin "3") (pinfunction "3_3") (pintype "passive"))
      (node (ref "J2") (pin "7") (pinfunction "7_7") (pintype "passive"))
      (node (ref "PCB1") (pin "GND") (pinfunction "GND_GND") (pintype "bidirectional"))
      (node (ref "PCB1") (pin "GND.") (pinfunction "GND._GND.") (pintype "bidirectional"))
      (node (ref "PCB1") (pin "GND..") (pinfunction "GND.._GND..") (pintype "bidirectional"))
      (node (ref "PCB1") (pin "GND...") (pinfunction "GND..._GND...") (pintype "bidirectional"))
      (node (ref "PCB1") (pin "GND....") (pinfunction "GND...._GND....") (pintype "bidirectional"))
      (node (ref "PCB1") (pin "GND__") (pinfunction "GND___GND__") (pintype "bidirectional"))
      (node (ref "R100") (pin "1") (pinfunction "1_1") (pintype "passive"))
      (node (ref "R101") (pin "2") (pinfunction "2_2") (pintype "passive"))
      (node (ref "R102") (pin "2") (pinfunction "2_2") (pintype "passive"))
      (node (ref "R103") (pin "2") (pinfunction "2_2") (pintype "passive"))
      (node (ref "R104") (pin "2") (pinfunction "2_2") (pintype "passive"))
      (node (ref "R105") (pin "2") (pinfunction "2_2") (pintype "passive"))
      (node (ref "R106") (pin "2") (pinfunction "2_2") (pintype "passive"))
      (node (ref "R107") (pin "2") (pinfunction "2_2") (pintype "passive"))
      (node (ref "R108") (pin "2") (pinfunction "2_2") (pintype "passive"))
      (node (ref "R109") (pin "2") (pinfunction "2_2") (pintype "passive"))
      (node (ref "R110") (pin "2") (pinfunction "2_2") (pintype "passive"))
      (node (ref "R111") (pin "2") (pinfunction "2_2") (pintype "passive"))
      (node (ref "R112") (pin "2") (pinfunction "2_2") (pintype "passive"))
      (node (ref "R113") (pin "2") (pinfunction "2_2") (pintype "passive"))
      (node (ref "R114") (pin "2") (pinfunction "2_2") (pintype "passive"))
      (node (ref "R115") (pin "2") (pinfunction "2_2") (pintype "passive"))
      (node (ref "R116") (pin "2") (pinfunction "2_2") (pintype "passive"))
      (node (ref "S10") (pin "P2") (pinfunction "P2_P2") (pintype "bidirectional"))
      (node (ref "S11") (pin "P2") (pinfunction "P2_P2") (pintype "bidirectional"))
      (node (ref "S12") (pin "P2") (pinfunction "P2_P2") (pintype "bidirectional"))
      (node (ref "S13") (pin "P2") (pinfunction "P2_P2") (pintype "bidirectional"))
      (node (ref "S14") (pin "P2") (pinfunction "P2_P2") (pintype "bidirectional"))
      (node (ref "S15") (pin "6") (pinfunction "6_6") (pintype "bidirectional"))
      (node (ref "S7") (pin "P2") (pinfunction "P2_P2") (pintype "bidirectional"))
      (node (ref "S8") (pin "P2") (pinfunction "P2_P2") (pintype "bidirectional"))
      (node (ref "S9") (pin "P2") (pinfunction "P2_P2") (pintype "bidirectional"))
      (node (ref "U100") (pin "9") (pinfunction "GND_9") (pintype "passive"))
      (node (ref "U101") (pin "9") (pinfunction "GND_9") (pintype "passive"))
      (node (ref "U102") (pin "9") (pinfunction "GND_9") (pintype "passive"))
      (node (ref "U103") (pin "9") (pinfunction "GND_9") (pintype "passive"))
      (node (ref "U104") (pin "9") (pinfunction "GND_9") (pintype "passive"))
    )
    (net (code "39") (name "HLDA") (class "Default")
      (node (ref "PCB1") (pin "22") (pinfunction "22_22") (pintype "bidirectional"))
      (node (ref "R150") (pin "1") (pinfunction "1_1") (pintype "passive"))
    )
    (net (code "40") (name "HLTA") (class "Default")
      (node (ref "PCB1") (pin "5") (pinfunction "5_5") (pintype "bidirectional"))
      (node (ref "R141") (pin "1") (pinfunction "1_1") (pintype "passive"))
    )
    (net (code "41") (name "INP") (class "Default")
      (node (ref "PCB1") (pin "8") (pinfunction "8_8") (pintype "bidirectional"))
      (node (ref "R146") (pin "1") (pinfunction "1_1") (pintype "passive"))
    )
    (net (code "42") (name "INT") (class "Default")
      (node (ref "PCB1") (pin "2") (pinfunction "2_2") (pintype "bidirectional"))
      (node (ref "R135") (pin "1") (pinfunction "1_1") (pintype "passive"))
    )
    (net (code "43") (name "INTE") (class "Default")
      (node (ref "PCB1") (pin "12") (pinfunction "12_12") (pintype "bidirectional"))
      (node (ref "R151") (pin "1") (pinfunction "1_1") (pintype "passive"))
    )
    (net (code "44") (name "IOREF") (class "Default")
      (node (ref "PCB1") (pin "I/OREF") (pinfunction "IOREF_I/OREF") (pintype "bidirectional"))
    )
    (net (code "45") (name "M1") (class "Default")
      (node (ref "PCB1") (pin "7") (pinfunction "7_7") (pintype "bidirectional"))
      (node (ref "R145") (pin "1") (pinfunction "1_1") (pintype "passive"))
    )
    (net (code "46") (name "MEMR") (class "Default")
      (node (ref "PCB1") (pin "9") (pinfunction "9_9") (pintype "bidirectional"))
      (node (ref "R148") (pin "1") (pinfunction "1_1") (pintype "passive"))
    )
    (net (code "47") (name "MISO") (class "Default")
      (node (ref "J2") (pin "5") (pinfunction "5_5") (pintype "passive"))
      (node (ref "PCB1") (pin "MISO") (pinfunction "MISO_MISO") (pintype "bidirectional"))
    )
    (net (code "48") (name "MOSI") (class "Default")
      (node (ref "J2") (pin "6") (pinfunction "6_6") (pintype "passive"))
      (node (ref "PCB1") (pin "MOSI") (pinfunction "MOSI_MOSI") (pintype "bidirectional"))
    )
    (net (code "49") (name "Net-(C100-Pad-)") (class "Default")
      (node (ref "C100") (pin "-") (pinfunction "-_-") (pintype "passive"))
      (node (ref "R100") (pin "2") (pinfunction "2_2") (pintype "passive"))
    )
    (net (code "50") (name "Net-(J3-Pad1)") (class "Default")
      (node (ref "J3") (pin "1") (pinfunction "1_1") (pintype "passive"))
      (node (ref "S15") (pin "5") (pinfunction "5_5") (pintype "bidirectional"))
    )
    (net (code "51") (name "Net-(J3-Pad2)") (class "Default")
      (node (ref "J3") (pin "2") (pinfunction "2_2") (pintype "passive"))
      (node (ref "S15") (pin "2") (pinfunction "2_2") (pintype "bidirectional"))
    )
    (net (code "52") (name "Net-(LED1-PadC)") (class "Default")
      (node (ref "LED1") (pin "C") (pinfunction "C_C") (pintype "passive"))
      (node (ref "R181") (pin "2") (pinfunction "2_2") (pintype "passive"))
    )
    (net (code "53") (name "Net-(LED2-PadC)") (class "Default")
      (node (ref "LED2") (pin "C") (pinfunction "C_C") (pintype "passive"))
      (node (ref "R180") (pin "2") (pinfunction "2_2") (pintype "passive"))
    )
    (net (code "54") (name "Net-(LED3-PadC)") (class "Default")
      (node (ref "LED3") (pin "C") (pinfunction "C_C") (pintype "passive"))
      (node (ref "R178") (pin "2") (pinfunction "2_2") (pintype "passive"))
    )
    (net (code "55") (name "Net-(LED4-PadC)") (class "Default")
      (node (ref "LED4") (pin "C") (pinfunction "C_C") (pintype "passive"))
      (node (ref "R176") (pin "2") (pinfunction "2_2") (pintype "passive"))
    )
    (net (code "56") (name "Net-(LED5-PadC)") (class "Default")
      (node (ref "LED5") (pin "C") (pinfunction "C_C") (pintype "passive"))
      (node (ref "R175") (pin "2") (pinfunction "2_2") (pintype "passive"))
    )
    (net (code "57") (name "Net-(LED6-PadC)") (class "Default")
      (node (ref "LED6") (pin "C") (pinfunction "C_C") (pintype "passive"))
      (node (ref "R173") (pin "2") (pinfunction "2_2") (pintype "passive"))
    )
    (net (code "58") (name "Net-(LED7-PadC)") (class "Default")
      (node (ref "LED7") (pin "C") (pinfunction "C_C") (pintype "passive"))
      (node (ref "R171") (pin "2") (pinfunction "2_2") (pintype "passive"))
    )
    (net (code "59") (name "Net-(LED8-PadC)") (class "Default")
      (node (ref "LED8") (pin "C") (pinfunction "C_C") (pintype "passive"))
      (node (ref "R169") (pin "2") (pinfunction "2_2") (pintype "passive"))
    )
    (net (code "60") (name "Net-(LED9-PadC)") (class "Default")
      (node (ref "LED9") (pin "C") (pinfunction "C_C") (pintype "passive"))
      (node (ref "R167") (pin "2") (pinfunction "2_2") (pintype "passive"))
    )
    (net (code "61") (name "Net-(LED10-PadC)") (class "Default")
      (node (ref "LED10") (pin "C") (pinfunction "C_C") (pintype "passive"))
      (node (ref "R165") (pin "2") (pinfunction "2_2") (pintype "passive"))
    )
    (net (code "62") (name "Net-(LED11-PadC)") (class "Default")
      (node (ref "LED11") (pin "C") (pinfunction "C_C") (pintype "passive"))
      (node (ref "R161") (pin "2") (pinfunction "2_2") (pintype "passive"))
    )
    (net (code "63") (name "Net-(LED12-PadC)") (class "Default")
      (node (ref "LED12") (pin "C") (pinfunction "C_C") (pintype "passive"))
      (node (ref "R159") (pin "2") (pinfunction "2_2") (pintype "passive"))
    )
    (net (code "64") (name "Net-(LED13-PadC)") (class "Default")
      (node (ref "LED13") (pin "C") (pinfunction "C_C") (pintype "passive"))
      (node (ref "R157") (pin "2") (pinfunction "2_2") (pintype "passive"))
    )
    (net (code "65") (name "Net-(LED14-PadC)") (class "Default")
      (node (ref "LED14") (pin "C") (pinfunction "C_C") (pintype "passive"))
      (node (ref "R155") (pin "2") (pinfunction "2_2") (pintype "passive"))
    )
    (net (code "66") (name "Net-(LED15-PadC)") (class "Default")
      (node (ref "LED15") (pin "C") (pinfunction "C_C") (pintype "passive"))
      (node (ref "R153") (pin "1") (pinfunction "1_1") (pintype "passive"))
    )
    (net (code "67") (name "Net-(LED16-PadC)") (class "Default")
      (node (ref "LED16") (pin "C") (pinfunction "C_C") (pintype "passive"))
      (node (ref "R187") (pin "1") (pinfunction "1_1") (pintype "passive"))
    )
    (net (code "68") (name "Net-(LED17-PadC)") (class "Default")
      (node (ref "LED17") (pin "C") (pinfunction "C_C") (pintype "passive"))
      (node (ref "R185") (pin "1") (pinfunction "1_1") (pintype "passive"))
    )
    (net (code "69") (name "Net-(LED18-PadC)") (class "Default")
      (node (ref "LED18") (pin "C") (pinfunction "C_C") (pintype "passive"))
      (node (ref "R183") (pin "1") (pinfunction "1_1") (pintype "passive"))
    )
    (net (code "70") (name "Net-(LED19-PadC)") (class "Default")
      (node (ref "LED19") (pin "C") (pinfunction "C_C") (pintype "passive"))
      (node (ref "R182") (pin "2") (pinfunction "2_2") (pintype "passive"))
    )
    (net (code "71") (name "Net-(LED20-PadC)") (class "Default")
      (node (ref "LED20") (pin "C") (pinfunction "C_C") (pintype "passive"))
      (node (ref "R179") (pin "2") (pinfunction "2_2") (pintype "passive"))
    )
    (net (code "72") (name "Net-(LED21-PadC)") (class "Default")
      (node (ref "LED21") (pin "C") (pinfunction "C_C") (pintype "passive"))
      (node (ref "R177") (pin "2") (pinfunction "2_2") (pintype "passive"))
    )
    (net (code "73") (name "Net-(LED22-PadC)") (class "Default")
      (node (ref "LED22") (pin "C") (pinfunction "C_C") (pintype "passive"))
      (node (ref "R174") (pin "2") (pinfunction "2_2") (pintype "passive"))
    )
    (net (code "74") (name "Net-(LED23-PadC)") (class "Default")
      (node (ref "LED23") (pin "C") (pinfunction "C_C") (pintype "passive"))
      (node (ref "R172") (pin "2") (pinfunction "2_2") (pintype "passive"))
    )
    (net (code "75") (name "Net-(LED24-PadC)") (class "Default")
      (node (ref "LED24") (pin "C") (pinfunction "C_C") (pintype "passive"))
      (node (ref "R170") (pin "2") (pinfunction "2_2") (pintype "passive"))
    )
    (net (code "76") (name "Net-(LED25-PadC)") (class "Default")
      (node (ref "LED25") (pin "C") (pinfunction "C_C") (pintype "passive"))
      (node (ref "R168") (pin "2") (pinfunction "2_2") (pintype "passive"))
    )
    (net (code "77") (name "Net-(LED26-PadC)") (class "Default")
      (node (ref "LED26") (pin "C") (pinfunction "C_C") (pintype "passive"))
      (node (ref "R166") (pin "2") (pinfunction "2_2") (pintype "passive"))
    )
    (net (code "78") (name "Net-(LED27-PadC)") (class "Default")
      (node (ref "LED27") (pin "C") (pinfunction "C_C") (pintype "passive"))
      (node (ref "R164") (pin "2") (pinfunction "2_2") (pintype "passive"))
    )
    (net (code "79") (name "Net-(LED28-PadC)") (class "Default")
      (node (ref "LED28") (pin "C") (pinfunction "C_C") (pintype "passive"))
      (node (ref "R163") (pin "2") (pinfunction "2_2") (pintype "passive"))
    )
    (net (code "80") (name "Net-(LED29-PadC)") (class "Default")
      (node (ref "LED29") (pin "C") (pinfunction "C_C") (pintype "passive"))
      (node (ref "R162") (pin "2") (pinfunction "2_2") (pintype "passive"))
    )
    (net (code "81") (name "Net-(LED30-PadC)") (class "Default")
      (node (ref "LED30") (pin "C") (pinfunction "C_C") (pintype "passive"))
      (node (ref "R160") (pin "2") (pinfunction "2_2") (pintype "passive"))
    )
    (net (code "82") (name "Net-(LED31-PadC)") (class "Default")
      (node (ref "LED31") (pin "C") (pinfunction "C_C") (pintype "passive"))
      (node (ref "R158") (pin "2") (pinfunction "2_2") (pintype "passive"))
    )
    (net (code "83") (name "Net-(LED32-PadC)") (class "Default")
      (node (ref "LED32") (pin "C") (pinfunction "C_C") (pintype "passive"))
      (node (ref "R156") (pin "2") (pinfunction "2_2") (pintype "passive"))
    )
    (net (code "84") (name "Net-(LED33-PadC)") (class "Default")
      (node (ref "LED33") (pin "C") (pinfunction "C_C") (pintype "passive"))
      (node (ref "R154") (pin "1") (pinfunction "1_1") (pintype "passive"))
    )
    (net (code "85") (name "Net-(LED34-PadC)") (class "Default")
      (node (ref "LED34") (pin "C") (pinfunction "C_C") (pintype "passive"))
      (node (ref "R188") (pin "1") (pinfunction "1_1") (pintype "passive"))
    )
    (net (code "86") (name "Net-(LED35-PadC)") (class "Default")
      (node (ref "LED35") (pin "C") (pinfunction "C_C") (pintype "passive"))
      (node (ref "R186") (pin "1") (pinfunction "1_1") (pintype "passive"))
    )
    (net (code "87") (name "Net-(LED36-PadC)") (class "Default")
      (node (ref "LED36") (pin "C") (pinfunction "C_C") (pintype "passive"))
      (node (ref "R184") (pin "1") (pinfunction "1_1") (pintype "passive"))
    )
    (net (code "88") (name "Net-(U100-1B)") (class "Default")
      (node (ref "R117") (pin "2") (pinfunction "2_2") (pintype "passive"))
      (node (ref "U100") (pin "1") (pinfunction "1B_1") (pintype "input"))
    )
    (net (code "89") (name "Net-(U100-1C)") (class "Default")
      (node (ref "R183") (pin "2") (pinfunction "2_2") (pintype "passive"))
      (node (ref "U100") (pin "18") (pinfunction "1C_18") (pintype "output"))
    )
    (net (code "90") (name "Net-(U100-2B)") (class "Default")
      (node (ref "R118") (pin "2") (pinfunction "2_2") (pintype "passive"))
      (node (ref "U100") (pin "2") (pinfunction "2B_2") (pintype "input"))
    )
    (net (code "91") (name "Net-(U100-2C)") (class "Default")
      (node (ref "R184") (pin "2") (pinfunction "2_2") (pintype "passive"))
      (node (ref "U100") (pin "17") (pinfunction "2C_17") (pintype "output"))
    )
    (net (code "92") (name "Net-(U100-3B)") (class "Default")
      (node (ref "R119") (pin "2") (pinfunction "2_2") (pintype "passive"))
      (node (ref "U100") (pin "3") (pinfunction "3B_3") (pintype "input"))
    )
    (net (code "93") (name "Net-(U100-3C)") (class "Default")
      (node (ref "R185") (pin "2") (pinfunction "2_2") (pintype "passive"))
      (node (ref "U100") (pin "16") (pinfunction "3C_16") (pintype "output"))
    )
    (net (code "94") (name "Net-(U100-4B)") (class "Default")
      (node (ref "R120") (pin "2") (pinfunction "2_2") (pintype "passive"))
      (node (ref "U100") (pin "4") (pinfunction "4B_4") (pintype "input"))
    )
    (net (code "95") (name "Net-(U100-4C)") (class "Default")
      (node (ref "R186") (pin "2") (pinfunction "2_2") (pintype "passive"))
      (node (ref "U100") (pin "15") (pinfunction "4C_15") (pintype "output"))
    )
    (net (code "96") (name "Net-(U100-5B)") (class "Default")
      (node (ref "R121") (pin "2") (pinfunction "2_2") (pintype "passive"))
      (node (ref "U100") (pin "5") (pinfunction "5B_5") (pintype "input"))
    )
    (net (code "97") (name "Net-(U100-5C)") (class "Default")
      (node (ref "R187") (pin "2") (pinfunction "2_2") (pintype "passive"))
      (node (ref "U100") (pin "14") (pinfunction "5C_14") (pintype "output"))
    )
    (net (code "98") (name "Net-(U100-6B)") (class "Default")
      (node (ref "R122") (pin "2") (pinfunction "2_2") (pintype "passive"))
      (node (ref "U100") (pin "6") (pinfunction "6B_6") (pintype "input"))
    )
    (net (code "99") (name "Net-(U100-6C)") (class "Default")
      (node (ref "R188") (pin "2") (pinfunction "2_2") (pintype "passive"))
      (node (ref "U100") (pin "13") (pinfunction "6C_13") (pintype "output"))
    )
    (net (code "100") (name "Net-(U100-7B)") (class "Default")
      (node (ref "R123") (pin "2") (pinfunction "2_2") (pintype "passive"))
      (node (ref "U100") (pin "7") (pinfunction "7B_7") (pintype "input"))
    )
    (net (code "101") (name "Net-(U100-7C)") (class "Default")
      (node (ref "R153") (pin "2") (pinfunction "2_2") (pintype "passive"))
      (node (ref "U100") (pin "12") (pinfunction "7C_12") (pintype "output"))
    )
    (net (code "102") (name "Net-(U100-8B)") (class "Default")
      (node (ref "R124") (pin "2") (pinfunction "2_2") (pintype "passive"))
      (node (ref "U100") (pin "8") (pinfunction "8B_8") (pintype "input"))
    )
    (net (code "103") (name "Net-(U100-8C)") (class "Default")
      (node (ref "R154") (pin "2") (pinfunction "2_2") (pintype "passive"))
      (node (ref "U100") (pin "11") (pinfunction "8C_11") (pintype "output"))
    )
    (net (code "104") (name "Net-(U101-1B)") (class "Default")
      (node (ref "R125") (pin "2") (pinfunction "2_2") (pintype "passive"))
      (node (ref "U101") (pin "1") (pinfunction "1B_1") (pintype "input"))
    )
    (net (code "105") (name "Net-(U101-1C)") (class "Default")
      (node (ref "R155") (pin "1") (pinfunction "1_1") (pintype "passive"))
      (node (ref "U101") (pin "18") (pinfunction "1C_18") (pintype "output"))
    )
    (net (code "106") (name "Net-(U101-2B)") (class "Default")
      (node (ref "R126") (pin "2") (pinfunction "2_2") (pintype "passive"))
      (node (ref "U101") (pin "2") (pinfunction "2B_2") (pintype "input"))
    )
    (net (code "107") (name "Net-(U101-2C)") (class "Default")
      (node (ref "R156") (pin "1") (pinfunction "1_1") (pintype "passive"))
      (node (ref "U101") (pin "17") (pinfunction "2C_17") (pintype "output"))
    )
    (net (code "108") (name "Net-(U101-3B)") (class "Default")
      (node (ref "R127") (pin "2") (pinfunction "2_2") (pintype "passive"))
      (node (ref "U101") (pin "3") (pinfunction "3B_3") (pintype "input"))
    )
    (net (code "109") (name "Net-(U101-3C)") (class "Default")
      (node (ref "R157") (pin "1") (pinfunction "1_1") (pintype "passive"))
      (node (ref "U101") (pin "16") (pinfunction "3C_16") (pintype "output"))
    )
    (net (code "110") (name "Net-(U101-4B)") (class "Default")
      (node (ref "R128") (pin "2") (pinfunction "2_2") (pintype "passive"))
      (node (ref "U101") (pin "4") (pinfunction "4B_4") (pintype "input"))
    )
    (net (code "111") (name "Net-(U101-4C)") (class "Default")
      (node (ref "R158") (pin "1") (pinfunction "1_1") (pintype "passive"))
      (node (ref "U101") (pin "15") (pinfunction "4C_15") (pintype "output"))
    )
    (net (code "112") (name "Net-(U101-5B)") (class "Default")
      (node (ref "R129") (pin "2") (pinfunction "2_2") (pintype "passive"))
      (node (ref "U101") (pin "5") (pinfunction "5B_5") (pintype "input"))
    )
    (net (code "113") (name "Net-(U101-5C)") (class "Default")
      (node (ref "R159") (pin "1") (pinfunction "1_1") (pintype "passive"))
      (node (ref "U101") (pin "14") (pinfunction "5C_14") (pintype "output"))
    )
    (net (code "114") (name "Net-(U101-6B)") (class "Default")
      (node (ref "R130") (pin "2") (pinfunction "2_2") (pintype "passive"))
      (node (ref "U101") (pin "6") (pinfunction "6B_6") (pintype "input"))
    )
    (net (code "115") (name "Net-(U101-6C)") (class "Default")
      (node (ref "R160") (pin "1") (pinfunction "1_1") (pintype "passive"))
      (node (ref "U101") (pin "13") (pinfunction "6C_13") (pintype "output"))
    )
    (net (code "116") (name "Net-(U101-7B)") (class "Default")
      (node (ref "R131") (pin "2") (pinfunction "2_2") (pintype "passive"))
      (node (ref "U101") (pin "7") (pinfunction "7B_7") (pintype "input"))
    )
    (net (code "117") (name "Net-(U101-7C)") (class "Default")
      (node (ref "R161") (pin "1") (pinfunction "1_1") (pintype "passive"))
      (node (ref "U101") (pin "12") (pinfunction "7C_12") (pintype "output"))
    )
    (net (code "118") (name "Net-(U101-8B)") (class "Default")
      (node (ref "R132") (pin "2") (pinfunction "2_2") (pintype "passive"))
      (node (ref "U101") (pin "8") (pinfunction "8B_8") (pintype "input"))
    )
    (net (code "119") (name "Net-(U101-8C)") (class "Default")
      (node (ref "R162") (pin "1") (pinfunction "1_1") (pintype "passive"))
      (node (ref "U101") (pin "11") (pinfunction "8C_11") (pintype "output"))
    )
    (net (code "120") (name "Net-(U102-1B)") (class "Default")
      (node (ref "R133") (pin "2") (pinfunction "2_2") (pintype "passive"))
      (node (ref "U102") (pin "1") (pinfunction "1B_1") (pintype "input"))
    )
    (net (code "121") (name "Net-(U102-1C)") (class "Default")
      (node (ref "R163") (pin "1") (pinfunction "1_1") (pintype "passive"))
      (node (ref "U102") (pin "18") (pinfunction "1C_18") (pintype "output"))
    )
    (net (code "122") (name "Net-(U102-2B)") (class "Default")
      (node (ref "R134") (pin "2") (pinfunction "2_2") (pintype "passive"))
      (node (ref "U102") (pin "2") (pinfunction "2B_2") (pintype "input"))
    )
    (net (code "123") (name "Net-(U102-2C)") (class "Default")
      (node (ref "R164") (pin "1") (pinfunction "1_1") (pintype "passive"))
      (node (ref "U102") (pin "17") (pinfunction "2C_17") (pintype "output"))
    )
    (net (code "124") (name "Net-(U102-3B)") (class "Default")
      (node (ref "R135") (pin "2") (pinfunction "2_2") (pintype "passive"))
      (node (ref "U102") (pin "3") (pinfunction "3B_3") (pintype "input"))
    )
    (net (code "125") (name "Net-(U102-3C)") (class "Default")
      (node (ref "R165") (pin "1") (pinfunction "1_1") (pintype "passive"))
      (node (ref "U102") (pin "16") (pinfunction "3C_16") (pintype "output"))
    )
    (net (code "126") (name "Net-(U102-4B)") (class "Default")
      (node (ref "R136") (pin "2") (pinfunction "2_2") (pintype "passive"))
      (node (ref "U102") (pin "4") (pinfunction "4B_4") (pintype "input"))
    )
    (net (code "127") (name "Net-(U102-4C)") (class "Default")
      (node (ref "R166") (pin "1") (pinfunction "1_1") (pintype "passive"))
      (node (ref "U102") (pin "15") (pinfunction "4C_15") (pintype "output"))
    )
    (net (code "128") (name "Net-(U103-1B)") (class "Default")
      (node (ref "R137") (pin "2") (pinfunction "2_2") (pintype "passive"))
      (node (ref "U103") (pin "1") (pinfunction "1B_1") (pintype "input"))
    )
    (net (code "129") (name "Net-(U103-1C)") (class "Default")
      (node (ref "R167") (pin "1") (pinfunction "1_1") (pintype "passive"))
      (node (ref "U103") (pin "18") (pinfunction "1C_18") (pintype "output"))
    )
    (net (code "130") (name "Net-(U103-2B)") (class "Default")
      (node (ref "R138") (pin "2") (pinfunction "2_2") (pintype "passive"))
      (node (ref "U103") (pin "2") (pinfunction "2B_2") (pintype "input"))
    )
    (net (code "131") (name "Net-(U103-2C)") (class "Default")
      (node (ref "R168") (pin "1") (pinfunction "1_1") (pintype "passive"))
      (node (ref "U103") (pin "17") (pinfunction "2C_17") (pintype "output"))
    )
    (net (code "132") (name "Net-(U103-3B)") (class "Default")
      (node (ref "R139") (pin "2") (pinfunction "2_2") (pintype "passive"))
      (node (ref "U103") (pin "3") (pinfunction "3B_3") (pintype "input"))
    )
    (net (code "133") (name "Net-(U103-3C)") (class "Default")
      (node (ref "R169") (pin "1") (pinfunction "1_1") (pintype "passive"))
      (node (ref "U103") (pin "16") (pinfunction "3C_16") (pintype "output"))
    )
    (net (code "134") (name "Net-(U103-4B)") (class "Default")
      (node (ref "R140") (pin "2") (pinfunction "2_2") (pintype "passive"))
      (node (ref "U103") (pin "4") (pinfunction "4B_4") (pintype "input"))
    )
    (net (code "135") (name "Net-(U103-4C)") (class "Default")
      (node (ref "R170") (pin "1") (pinfunction "1_1") (pintype "passive"))
      (node (ref "U103") (pin "15") (pinfunction "4C_15") (pintype "output"))
    )
    (net (code "136") (name "Net-(U103-5B)") (class "Default")
      (node (ref "R141") (pin "2") (pinfunction "2_2") (pintype "passive"))
      (node (ref "U103") (pin "5") (pinfunction "5B_5") (pintype "input"))
    )
    (net (code "137") (name "Net-(U103-5C)") (class "Default")
      (node (ref "R171") (pin "1") (pinfunction "1_1") (pintype "passive"))
      (node (ref "U103") (pin "14") (pinfunction "5C_14") (pintype "output"))
    )
    (net (code "138") (name "Net-(U103-6B)") (class "Default")
      (node (ref "R142") (pin "2") (pinfunction "2_2") (pintype "passive"))
      (node (ref "U103") (pin "6") (pinfunction "6B_6") (pintype "input"))
    )
    (net (code "139") (name "Net-(U103-6C)") (class "Default")
      (node (ref "R172") (pin "1") (pinfunction "1_1") (pintype "passive"))
      (node (ref "U103") (pin "13") (pinfunction "6C_13") (pintype "output"))
    )
    (net (code "140") (name "Net-(U103-7B)") (class "Default")
      (node (ref "R143") (pin "2") (pinfunction "2_2") (pintype "passive"))
      (node (ref "U103") (pin "7") (pinfunction "7B_7") (pintype "input"))
    )
    (net (code "141") (name "Net-(U103-7C)") (class "Default")
      (node (ref "R173") (pin "1") (pinfunction "1_1") (pintype "passive"))
      (node (ref "U103") (pin "12") (pinfunction "7C_12") (pintype "output"))
    )
    (net (code "142") (name "Net-(U103-8B)") (class "Default")
      (node (ref "R144") (pin "2") (pinfunction "2_2") (pintype "passive"))
      (node (ref "U103") (pin "8") (pinfunction "8B_8") (pintype "input"))
    )
    (net (code "143") (name "Net-(U103-8C)") (class "Default")
      (node (ref "R174") (pin "1") (pinfunction "1_1") (pintype "passive"))
      (node (ref "U103") (pin "11") (pinfunction "8C_11") (pintype "output"))
    )
    (net (code "144") (name "Net-(U104-1B)") (class "Default")
      (node (ref "R145") (pin "2") (pinfunction "2_2") (pintype "passive"))
      (node (ref "U104") (pin "1") (pinfunction "1B_1") (pintype "input"))
    )
    (net (code "145") (name "Net-(U104-1C)") (class "Default")
      (node (ref "R175") (pin "1") (pinfunction "1_1") (pintype "passive"))
      (node (ref "U104") (pin "18") (pinfunction "1C_18") (pintype "output"))
    )
    (net (code "146") (name "Net-(U104-2B)") (class "Default")
      (node (ref "R146") (pin "2") (pinfunction "2_2") (pintype "passive"))
      (node (ref "U104") (pin "2") (pinfunction "2B_2") (pintype "input"))
    )
    (net (code "147") (name "Net-(U104-2C)") (class "Default")
      (node (ref "R176") (pin "1") (pinfunction "1_1") (pintype "passive"))
      (node (ref "U104") (pin "17") (pinfunction "2C_17") (pintype "output"))
    )
    (net (code "148") (name "Net-(U104-3B)") (class "Default")
      (node (ref "R147") (pin "2") (pinfunction "2_2") (pintype "passive"))
      (node (ref "U104") (pin "3") (pinfunction "3B_3") (pintype "input"))
    )
    (net (code "149") (name "Net-(U104-3C)") (class "Default")
      (node (ref "R177") (pin "1") (pinfunction "1_1") (pintype "passive"))
      (node (ref "U104") (pin "16") (pinfunction "3C_16") (pintype "output"))
    )
    (net (code "150") (name "Net-(U104-4B)") (class "Default")
      (node (ref "R148") (pin "2") (pinfunction "2_2") (pintype "passive"))
      (node (ref "U104") (pin "4") (pinfunction "4B_4") (pintype "input"))
    )
    (net (code "151") (name "Net-(U104-4C)") (class "Default")
      (node (ref "R178") (pin "1") (pinfunction "1_1") (pintype "passive"))
      (node (ref "U104") (pin "15") (pinfunction "4C_15") (pintype "output"))
    )
    (net (code "152") (name "Net-(U104-5B)") (class "Default")
      (node (ref "R149") (pin "2") (pinfunction "2_2") (pintype "passive"))
      (node (ref "U104") (pin "5") (pinfunction "5B_5") (pintype "input"))
    )
    (net (code "153") (name "Net-(U104-5C)") (class "Default")
      (node (ref "R179") (pin "1") (pinfunction "1_1") (pintype "passive"))
      (node (ref "U104") (pin "14") (pinfunction "5C_14") (pintype "output"))
    )
    (net (code "154") (name "Net-(U104-6B)") (class "Default")
      (node (ref "R150") (pin "2") (pinfunction "2_2") (pintype "passive"))
      (node (ref "U104") (pin "6") (pinfunction "6B_6") (pintype "input"))
    )
    (net (code "155") (name "Net-(U104-6C)") (class "Default")
      (node (ref "R180") (pin "1") (pinfunction "1_1") (pintype "passive"))
      (node (ref "U104") (pin "13") (pinfunction "6C_13") (pintype "output"))
    )
    (net (code "156") (name "Net-(U104-7B)") (class "Default")
      (node (ref "R151") (pin "2") (pinfunction "2_2") (pintype "passive"))
      (node (ref "U104") (pin "7") (pinfunction "7B_7") (pintype "input"))
    )
    (net (code "157") (name "Net-(U104-7C)") (class "Default")
      (node (ref "R181") (pin "1") (pinfunction "1_1") (pintype "passive"))
      (node (ref "U104") (pin "12") (pinfunction "7C_12") (pintype "output"))
    )
    (net (code "158") (name "Net-(U104-8B)") (class "Default")
      (node (ref "R152") (pin "2") (pinfunction "2_2") (pintype "passive"))
      (node (ref "U104") (pin "8") (pinfunction "8B_8") (pintype "input"))
    )
    (net (code "159") (name "Net-(U104-8C)") (class "Default")
      (node (ref "R182") (pin "1") (pinfunction "1_1") (pintype "passive"))
      (node (ref "U104") (pin "11") (pinfunction "8C_11") (pintype "output"))
    )
    (net (code "160") (name "OUT") (class "Default")
      (node (ref "PCB1") (pin "6") (pinfunction "6_6") (pintype "bidirectional"))
      (node (ref "R143") (pin "1") (pinfunction "1_1") (pintype "passive"))
    )
    (net (code "161") (name "PROT") (class "Default")
      (node (ref "PCB1") (pin "13") (pinfunction "13_13") (pintype "bidirectional"))
      (node (ref "R149") (pin "1") (pinfunction "1_1") (pintype "passive"))
    )
    (net (code "162") (name "PROTECT") (class "Default")
      (node (ref "PCB1") (pin "A6") (pinfunction "A6_A6") (pintype "bidirectional"))
      (node (ref "S12") (pin "P1") (pinfunction "P1_P1") (pintype "bidirectional"))
    )
    (net (code "163") (name "RESET") (class "Default")
      (node (ref "PCB1") (pin "52") (pinfunction "52_52") (pintype "bidirectional"))
      (node (ref "S11") (pin "P1") (pinfunction "P1_P1") (pintype "bidirectional"))
    )
    (net (code "164") (name "RUN") (class "Default")
      (node (ref "PCB1") (pin "20") (pinfunction "20(SDA)_20") (pintype "bidirectional"))
      (node (ref "S7") (pin "P3") (pinfunction "P3_P3") (pintype "bidirectional"))
    )
    (net (code "165") (name "SCK") (class "Default")
      (node (ref "J2") (pin "4") (pinfunction "4_4") (pintype "passive"))
      (node (ref "PCB1") (pin "SCK") (pinfunction "SCK_SCK") (pintype "bidirectional"))
    )
    (net (code "166") (name "SERIAL_RX") (class "Default")
      (node (ref "J1") (pin "3") (pinfunction "3_3") (pintype "passive"))
      (node (ref "PCB1") (pin "19") (pinfunction "19(RX1)_19") (pintype "bidirectional"))
    )
    (net (code "167") (name "SERIAL_TX") (class "Default")
      (node (ref "J1") (pin "4") (pinfunction "4_4") (pintype "passive"))
      (node (ref "PCB1") (pin "18") (pinfunction "18(TX1)_18") (pintype "bidirectional"))
    )
    (net (code "168") (name "SLOW") (class "Default")
      (node (ref "PCB1") (pin "A1") (pinfunction "A1_A1") (pintype "bidirectional"))
      (node (ref "S8") (pin "P3") (pinfunction "P3_P3") (pintype "bidirectional"))
    )
    (net (code "169") (name "STACK") (class "Default")
      (node (ref "PCB1") (pin "4") (pinfunction "4_4") (pintype "bidirectional"))
      (node (ref "R139") (pin "1") (pinfunction "1_1") (pintype "passive"))
    )
    (net (code "170") (name "STEP") (class "Default")
      (node (ref "PCB1") (pin "A0") (pinfunction "A0_A0") (pintype "bidirectional"))
      (node (ref "S8") (pin "P1") (pinfunction "P1_P1") (pintype "bidirectional"))
    )
    (net (code "171") (name "STOP") (class "Default")
      (node (ref "PCB1") (pin "21") (pinfunction "21(SCL)_21") (pintype "bidirectional"))
      (node (ref "S7") (pin "P1") (pinfunction "P1_P1") (pintype "bidirectional"))
    )
    (net (code "172") (name "SW0") (class "Default")
      (node (ref "PCB1") (pin "A8") (pinfunction "A8_A8") (pintype "bidirectional"))
      (node (ref "R101") (pin "1") (pinfunction "1_1") (pintype "passive"))
      (node (ref "S6") (pin "3") (pinfunction "3_3") (pintype "passive"))
    )
    (net (code "173") (name "SW1") (class "Default")
      (node (ref "PCB1") (pin "A9") (pinfunction "A9_A9") (pintype "bidirectional"))
      (node (ref "R102") (pin "1") (pinfunction "1_1") (pintype "passive"))
      (node (ref "S6") (pin "2") (pinfunction "2_2") (pintype "passive"))
    )
    (net (code "174") (name "SW2") (class "Default")
      (node (ref "PCB1") (pin "A10") (pinfunction "A10_A10") (pintype "bidirectional"))
      (node (ref "R103") (pin "1") (pinfunction "1_1") (pintype "passive"))
      (node (ref "S6") (pin "1") (pinfunction "1_1") (pintype "passive"))
    )
    (net (code "175") (name "SW3") (class "Default")
      (node (ref "PCB1") (pin "A11") (pinfunction "A11_A11") (pintype "bidirectional"))
      (node (ref "R104") (pin "1") (pinfunction "1_1") (pintype "passive"))
      (node (ref "S5") (pin "3") (pinfunction "3_3") (pintype "passive"))
    )
    (net (code "176") (name "SW4") (class "Default")
      (node (ref "PCB1") (pin "A12") (pinfunction "A12_A12") (pintype "bidirectional"))
      (node (ref "R105") (pin "1") (pinfunction "1_1") (pintype "passive"))
      (node (ref "S5") (pin "2") (pinfunction "2_2") (pintype "passive"))
    )
    (net (code "177") (name "SW5") (class "Default")
      (node (ref "PCB1") (pin "A13") (pinfunction "A13_A13") (pintype "bidirectional"))
      (node (ref "R106") (pin "1") (pinfunction "1_1") (pintype "passive"))
      (node (ref "S5") (pin "1") (pinfunction "1_1") (pintype "passive"))
    )
    (net (code "178") (name "SW6") (class "Default")
      (node (ref "PCB1") (pin "A14") (pinfunction "A14_A14") (pintype "bidirectional"))
      (node (ref "R107") (pin "1") (pinfunction "1_1") (pintype "passive"))
      (node (ref "S4") (pin "3") (pinfunction "3_3") (pintype "passive"))
    )
    (net (code "179") (name "SW7") (class "Default")
      (node (ref "PCB1") (pin "A15") (pinfunction "A15_A15") (pintype "bidirectional"))
      (node (ref "R108") (pin "1") (pinfunction "1_1") (pintype "passive"))
      (node (ref "S4") (pin "2") (pinfunction "2_2") (pintype "passive"))
    )
    (net (code "180") (name "SW8") (class "Default")
      (node (ref "PCB1") (pin "17") (pinfunction "17(RX2)_17") (pintype "bidirectional"))
      (node (ref "R109") (pin "1") (pinfunction "1_1") (pintype "passive"))
      (node (ref "S4") (pin "1") (pinfunction "1_1") (pintype "passive"))
    )
    (net (code "181") (name "SW9") (class "Default")
      (node (ref "PCB1") (pin "16") (pinfunction "16(TX2)_16") (pintype "bidirectional"))
      (node (ref "R110") (pin "1") (pinfunction "1_1") (pintype "passive"))
      (node (ref "S3") (pin "3") (pinfunction "3_3") (pintype "passive"))
    )
    (net (code "182") (name "SW10") (class "Default")
      (node (ref "PCB1") (pin "23") (pinfunction "23_23") (pintype "bidirectional"))
      (node (ref "R111") (pin "1") (pinfunction "1_1") (pintype "passive"))
      (node (ref "S3") (pin "2") (pinfunction "2_2") (pintype "passive"))
    )
    (net (code "183") (name "SW11") (class "Default")
      (node (ref "PCB1") (pin "24") (pinfunction "24_24") (pintype "bidirectional"))
      (node (ref "R112") (pin "1") (pinfunction "1_1") (pintype "passive"))
      (node (ref "S3") (pin "1") (pinfunction "1_1") (pintype "passive"))
    )
    (net (code "184") (name "SW12") (class "Default")
      (node (ref "PCB1") (pin "SDA1") (pinfunction "SDA1_SDA1") (pintype "bidirectional"))
      (node (ref "R113") (pin "1") (pinfunction "1_1") (pintype "passive"))
      (node (ref "S2") (pin "3") (pinfunction "3_3") (pintype "passive"))
    )
    (net (code "185") (name "SW13") (class "Default")
      (node (ref "PCB1") (pin "SCL1") (pinfunction "SCL1_SCL1") (pintype "bidirectional"))
      (node (ref "R114") (pin "1") (pinfunction "1_1") (pintype "passive"))
      (node (ref "S2") (pin "2") (pinfunction "2_2") (pintype "passive"))
    )
    (net (code "186") (name "SW14") (class "Default")
      (node (ref "PCB1") (pin "42") (pinfunction "42_42") (pintype "bidirectional"))
      (node (ref "R115") (pin "1") (pinfunction "1_1") (pintype "passive"))
      (node (ref "S2") (pin "1") (pinfunction "1_1") (pintype "passive"))
    )
    (net (code "187") (name "SW15") (class "Default")
      (node (ref "PCB1") (pin "43") (pinfunction "43_43") (pintype "bidirectional"))
      (node (ref "R116") (pin "1") (pinfunction "1_1") (pintype "passive"))
      (node (ref "S1") (pin "1") (pinfunction "1_1") (pintype "passive"))
    )
    (net (code "188") (name "UNPROTECT") (class "Default")
      (node (ref "PCB1") (pin "A7") (pinfunction "A7_A7") (pintype "bidirectional"))
      (node (ref "S12") (pin "P3") (pinfunction "P3_P3") (pintype "bidirectional"))
    )
    (net (code "189") (name "VCC") (class "Default")
      (node (ref "PCB1") (pin "3.3V") (pinfunction "3.3V_3.3V") (pintype "bidirectional"))
      (node (ref "S1") (pin "2") (pinfunction "2_2") (pintype "passive"))
      (node (ref "S2") (pin "4") (pinfunction "4_4") (pintype "passive"))
      (node (ref "S2") (pin "5") (pinfunction "5_5") (pintype "passive"))
      (node (ref "S2") (pin "6") (pinfunction "6_6") (pintype "passive"))
      (node (ref "S3") (pin "4") (pinfunction "4_4") (pintype "passive"))
      (node (ref "S3") (pin "5") (pinfunction "5_5") (pintype "passive"))
      (node (ref "S3") (pin "6") (pinfunction "6_6") (pintype "passive"))
      (node (ref "S4") (pin "4") (pinfunction "4_4") (pintype "passive"))
      (node (ref "S4") (pin "5") (pinfunction "5_5") (pintype "passive"))
      (node (ref "S4") (pin "6") (pinfunction "6_6") (pintype "passive"))
      (node (ref "S5") (pin "4") (pinfunction "4_4") (pintype "passive"))
      (node (ref "S5") (pin "5") (pinfunction "5_5") (pintype "passive"))
      (node (ref "S5") (pin "6") (pinfunction "6_6") (pintype "passive"))
      (node (ref "S6") (pin "4") (pinfunction "4_4") (pintype "passive"))
      (node (ref "S6") (pin "5") (pinfunction "5_5") (pintype "passive"))
      (node (ref "S6") (pin "6") (pinfunction "6_6") (pintype "passive"))
    )
    (net (code "190") (name "VIN") (class "Default")
      (node (ref "PCB1") (pin "VIN") (pinfunction "VIN_VIN") (pintype "bidirectional"))
      (node (ref "S15") (pin "3") (pinfunction "3_3") (pintype "bidirectional"))
    )
    (net (code "191") (name "WAIT") (class "Default")
      (node (ref "PCB1") (pin "10") (pinfunction "10_10") (pintype "bidirectional"))
      (node (ref "R152") (pin "1") (pinfunction "1_1") (pintype "passive"))
    )
    (net (code "192") (name "WO") (class "Default")
      (node (ref "PCB1") (pin "3") (pinfunction "3_3") (pintype "bidirectional"))
      (node (ref "R137") (pin "1") (pinfunction "1_1") (pintype "passive"))
    )
    (net (code "193") (name "unconnected-(J1-Pad5)") (class "Default")
      (node (ref "J1") (pin "5") (pinfunction "5_5") (pintype "passive"))
    )
    (net (code "194") (name "unconnected-(J1-Pad6)") (class "Default")
      (node (ref "J1") (pin "6") (pinfunction "6_6") (pintype "passive"))
    )
    (net (code "195") (name "unconnected-(J2-Pad2)") (class "Default")
      (node (ref "J2") (pin "2") (pinfunction "2_2") (pintype "passive"))
    )
    (net (code "196") (name "unconnected-(J2-Pad8)") (class "Default")
      (node (ref "J2") (pin "8") (pinfunction "8_8") (pintype "passive"))
    )
    (net (code "197") (name "unconnected-(PCB1-(N{slash}C)-PadN{slash}C)") (class "Default")
      (node (ref "PCB1") (pin "N/C") (pinfunction "(N/C)_N/C") (pintype "bidirectional"))
    )
    (net (code "198") (name "unconnected-(PCB1-0(RX)-Pad0)") (class "Default")
      (node (ref "PCB1") (pin "0") (pinfunction "0(RX)_0") (pintype "bidirectional"))
    )
    (net (code "199") (name "unconnected-(PCB1-1(TX)-Pad1)") (class "Default")
      (node (ref "PCB1") (pin "1") (pinfunction "1(TX)_1") (pintype "bidirectional"))
    )
    (net (code "200") (name "unconnected-(PCB1-PadRESET.)") (class "Default")
      (node (ref "PCB1") (pin "RESET.") (pinfunction "RESET._RESET.") (pintype "bidirectional"))
    )
    (net (code "201") (name "unconnected-(S15-Pad1)") (class "Default")
      (node (ref "S15") (pin "1") (pinfunction "1_1") (pintype "bidirectional"))
    )
    (net (code "202") (name "unconnected-(S15-Pad4)") (class "Default")
      (node (ref "S15") (pin "4") (pinfunction "4_4") (pintype "bidirectional"))
    )
    (net (code "203") (name "unconnected-(U102-5B-Pad5)") (class "Default")
      (node (ref "U102") (pin "5") (pinfunction "5B_5") (pintype "input"))
    )
    (net (code "204") (name "unconnected-(U102-5C-Pad14)") (class "Default")
      (node (ref "U102") (pin "14") (pinfunction "5C_14") (pintype "output"))
    )
    (net (code "205") (name "unconnected-(U102-6B-Pad6)") (class "Default")
      (node (ref "U102") (pin "6") (pinfunction "6B_6") (pintype "input"))
    )
    (net (code "206") (name "unconnected-(U102-6C-Pad13)") (class "Default")
      (node (ref "U102") (pin "13") (pinfunction "6C_13") (pintype "output"))
    )
    (net (code "207") (name "unconnected-(U102-7B-Pad7)") (class "Default")
      (node (ref "U102") (pin "7") (pinfunction "7B_7") (pintype "input"))
    )
    (net (code "208") (name "unconnected-(U102-7C-Pad12)") (class "Default")
      (node (ref "U102") (pin "12") (pinfunction "7C_12") (pintype "output"))
    )
    (net (code "209") (name "unconnected-(U102-8B-Pad8)") (class "Default")
      (node (ref "U102") (pin "8") (pinfunction "8B_8") (pintype "input"))
    )
    (net (code "210") (name "unconnected-(U102-8C-Pad11)") (class "Default")
      (node (ref "U102") (pin "11") (pinfunction "8C_11") (pintype "output"))
    )
  )
)
